# Sheet1.net
KiCad netlist of a schematic drawn in Altium Designer
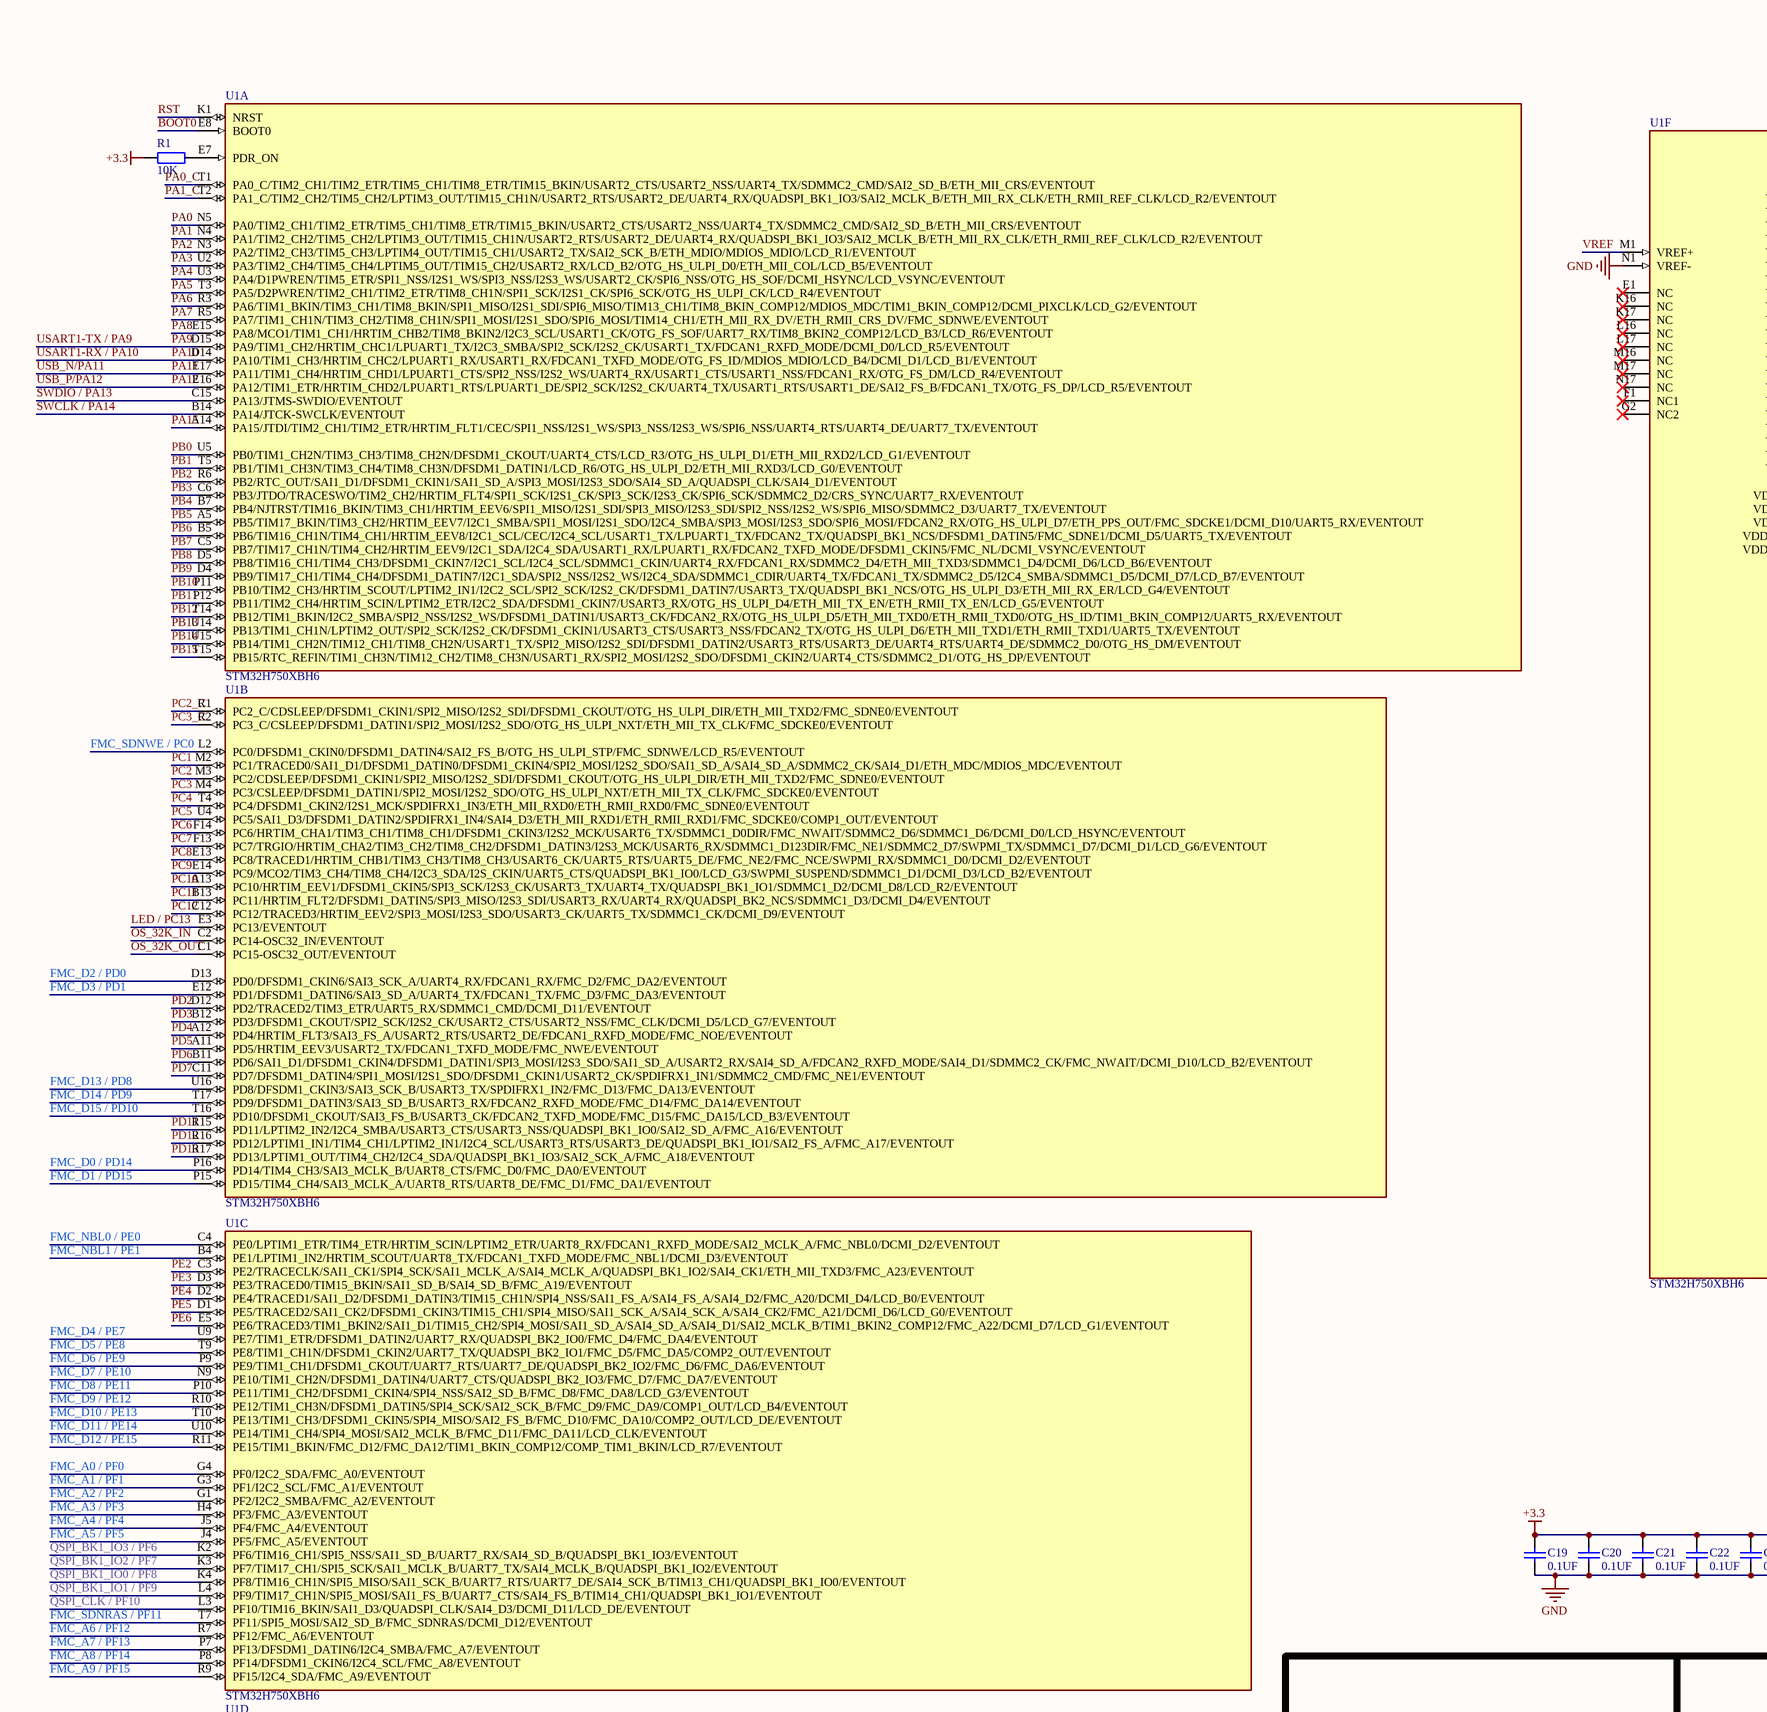
[diagram p0: Sheet1.SchDoc, top left]
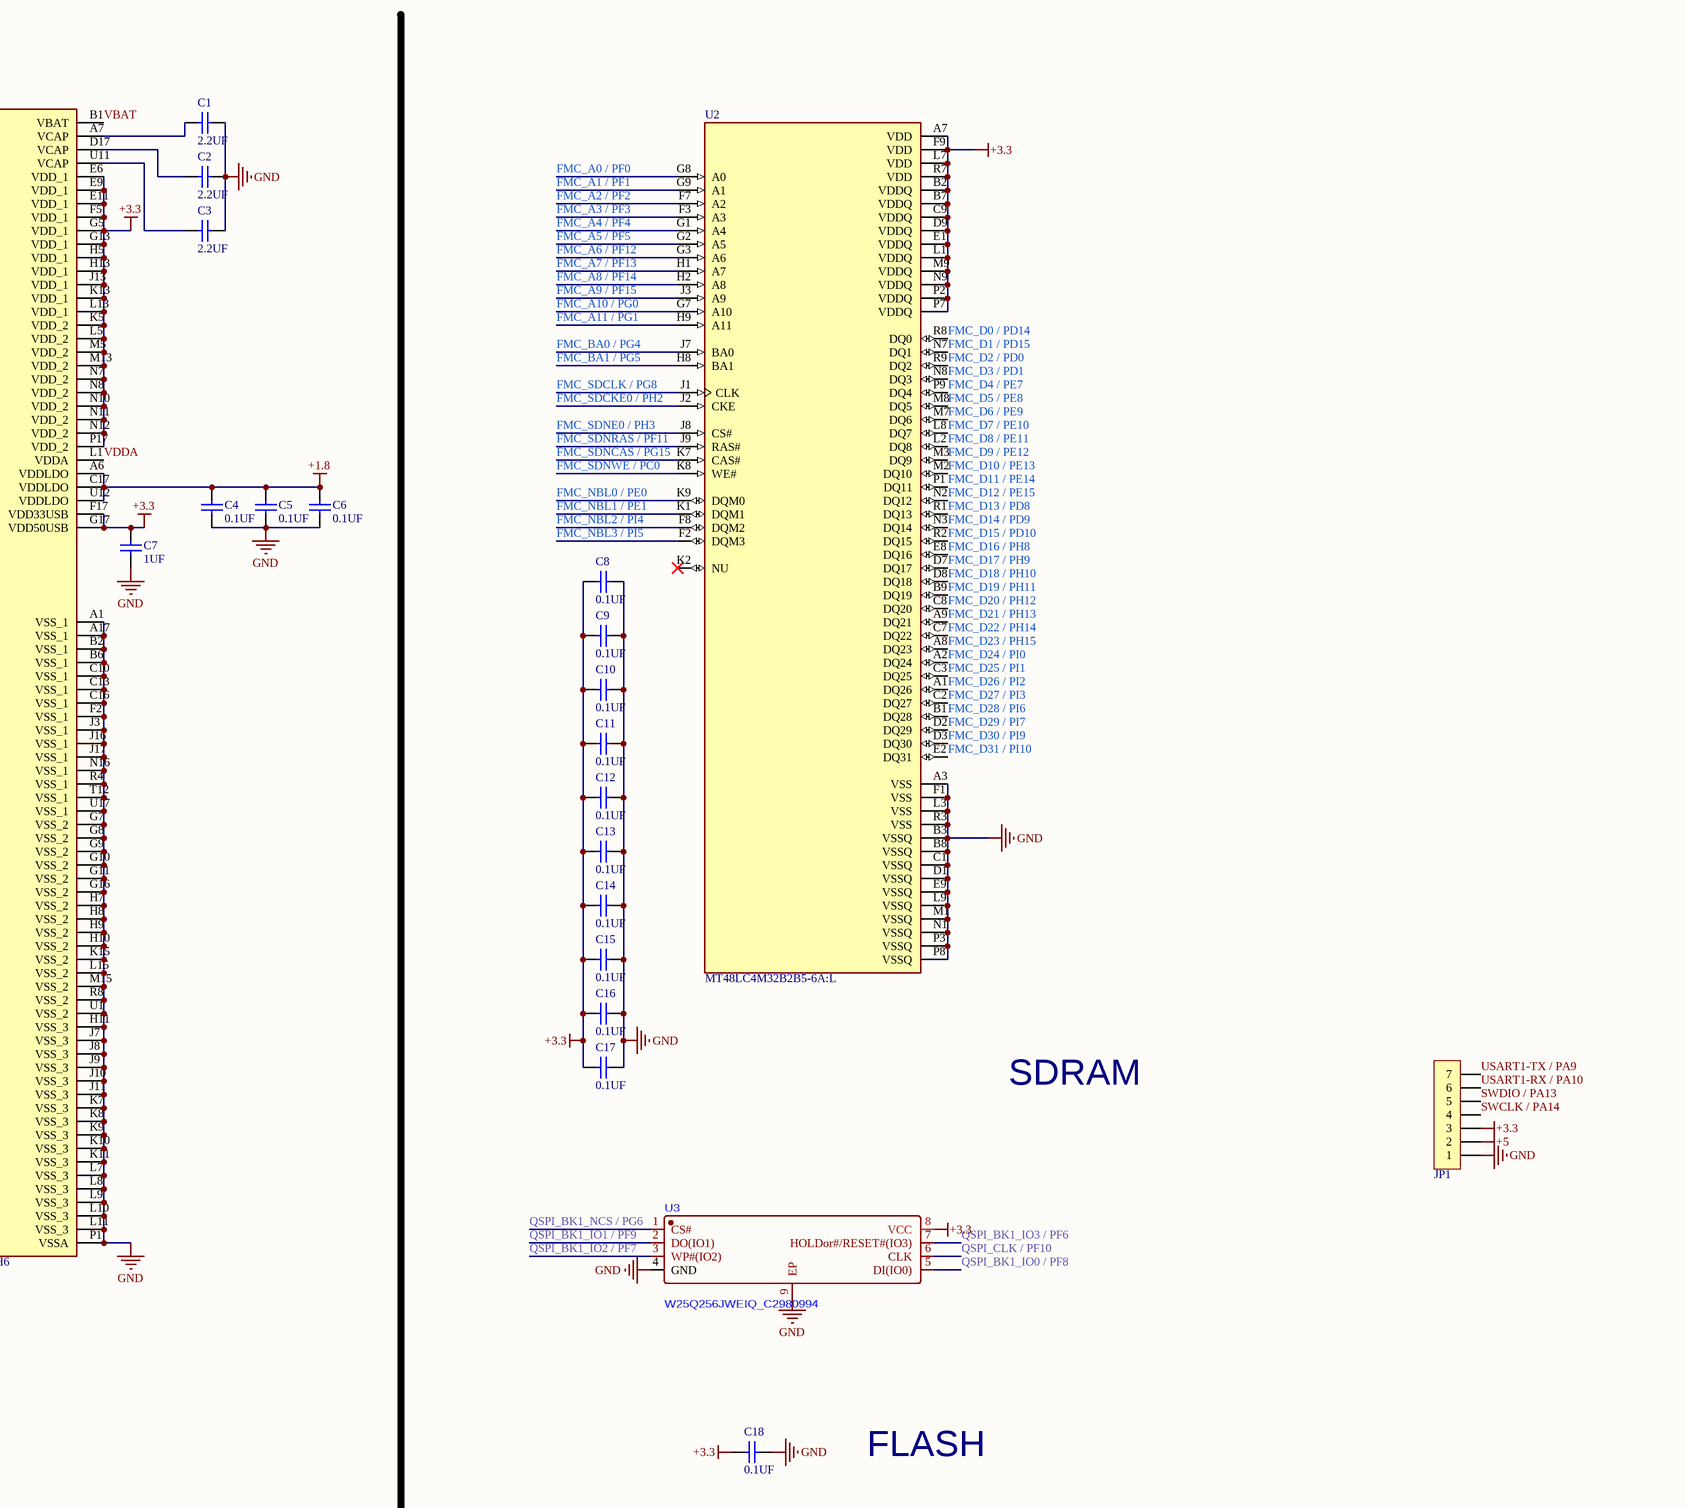
[diagram p1: Sheet1.SchDoc, top right]
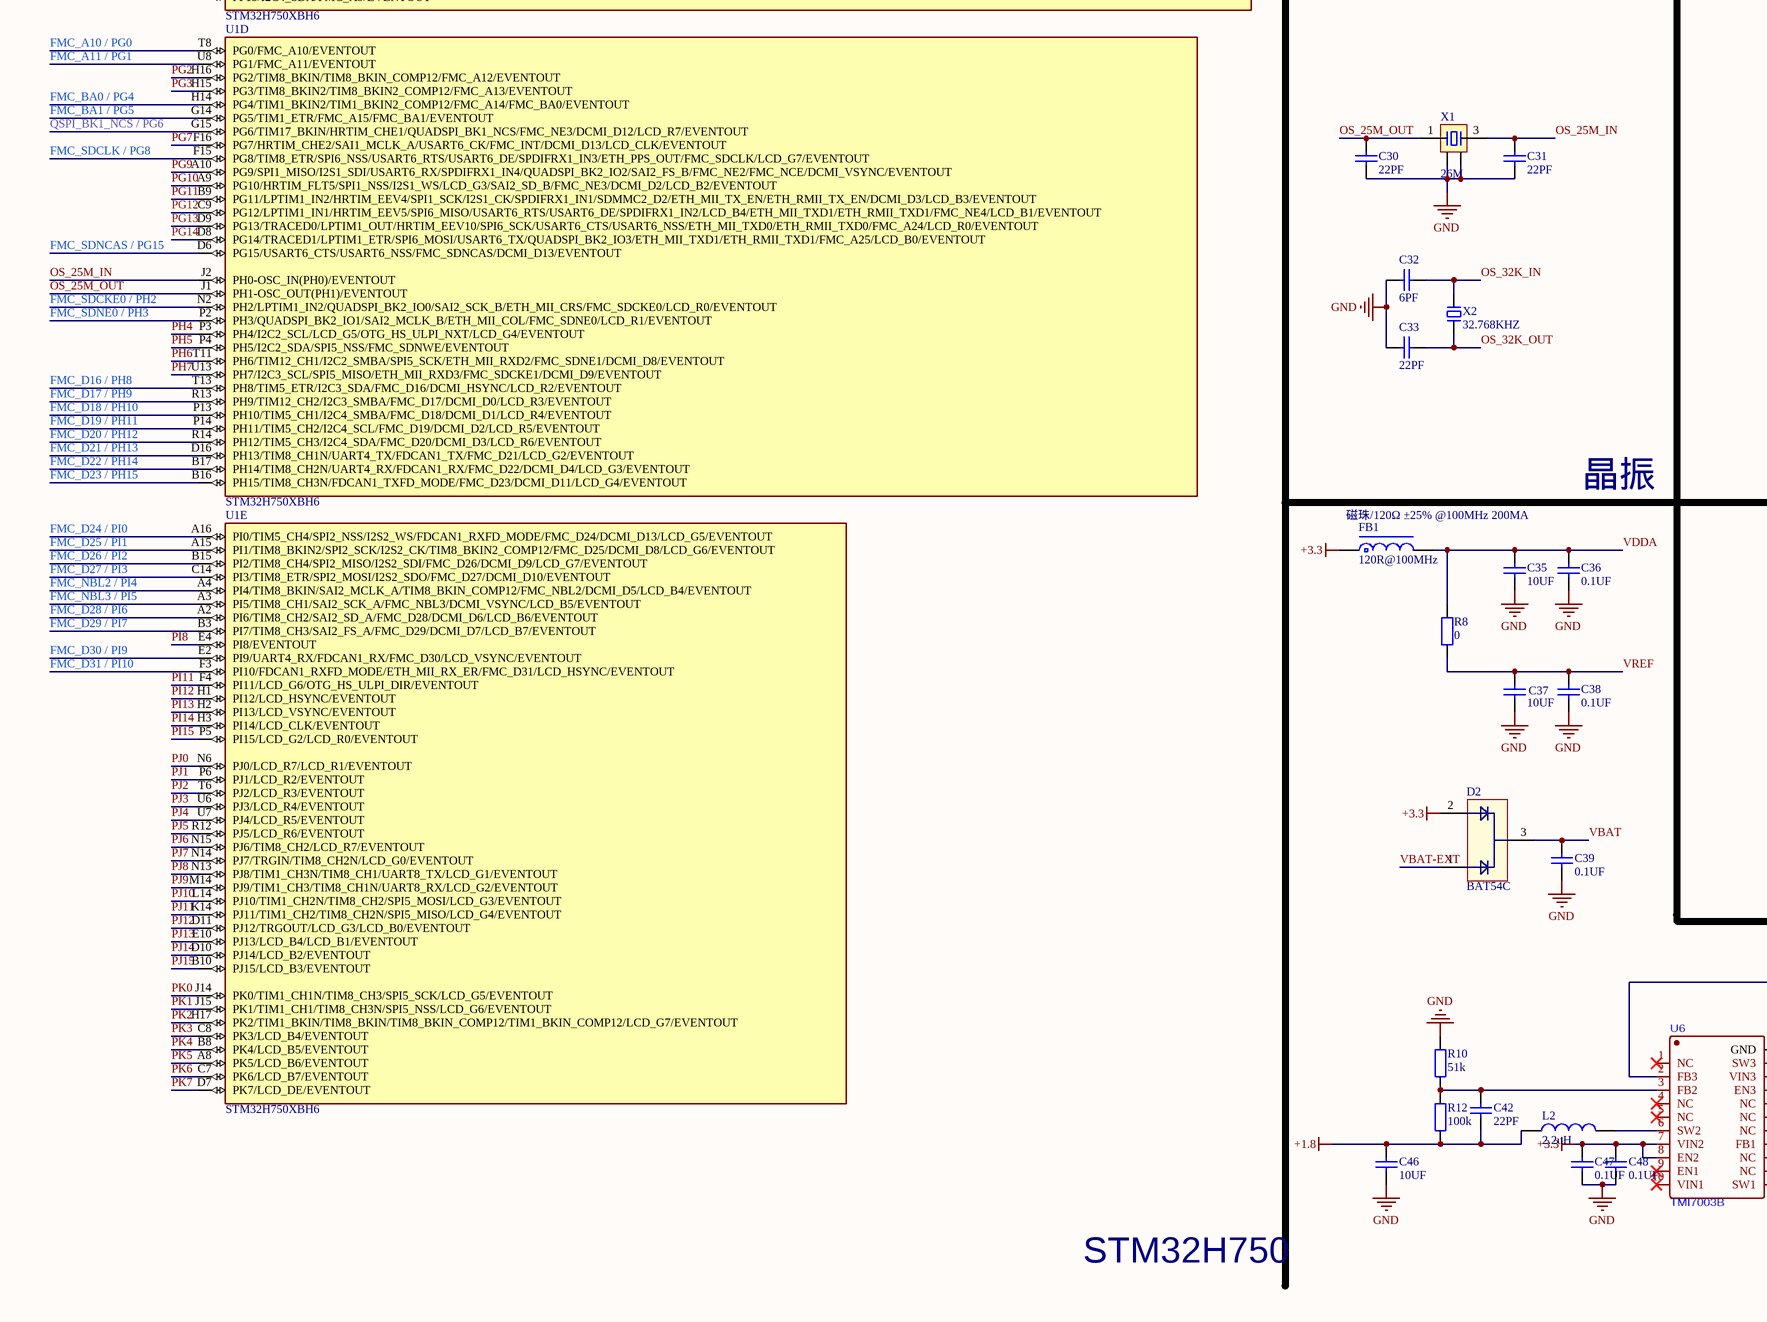
[diagram p2: Sheet1.SchDoc, bottom left]
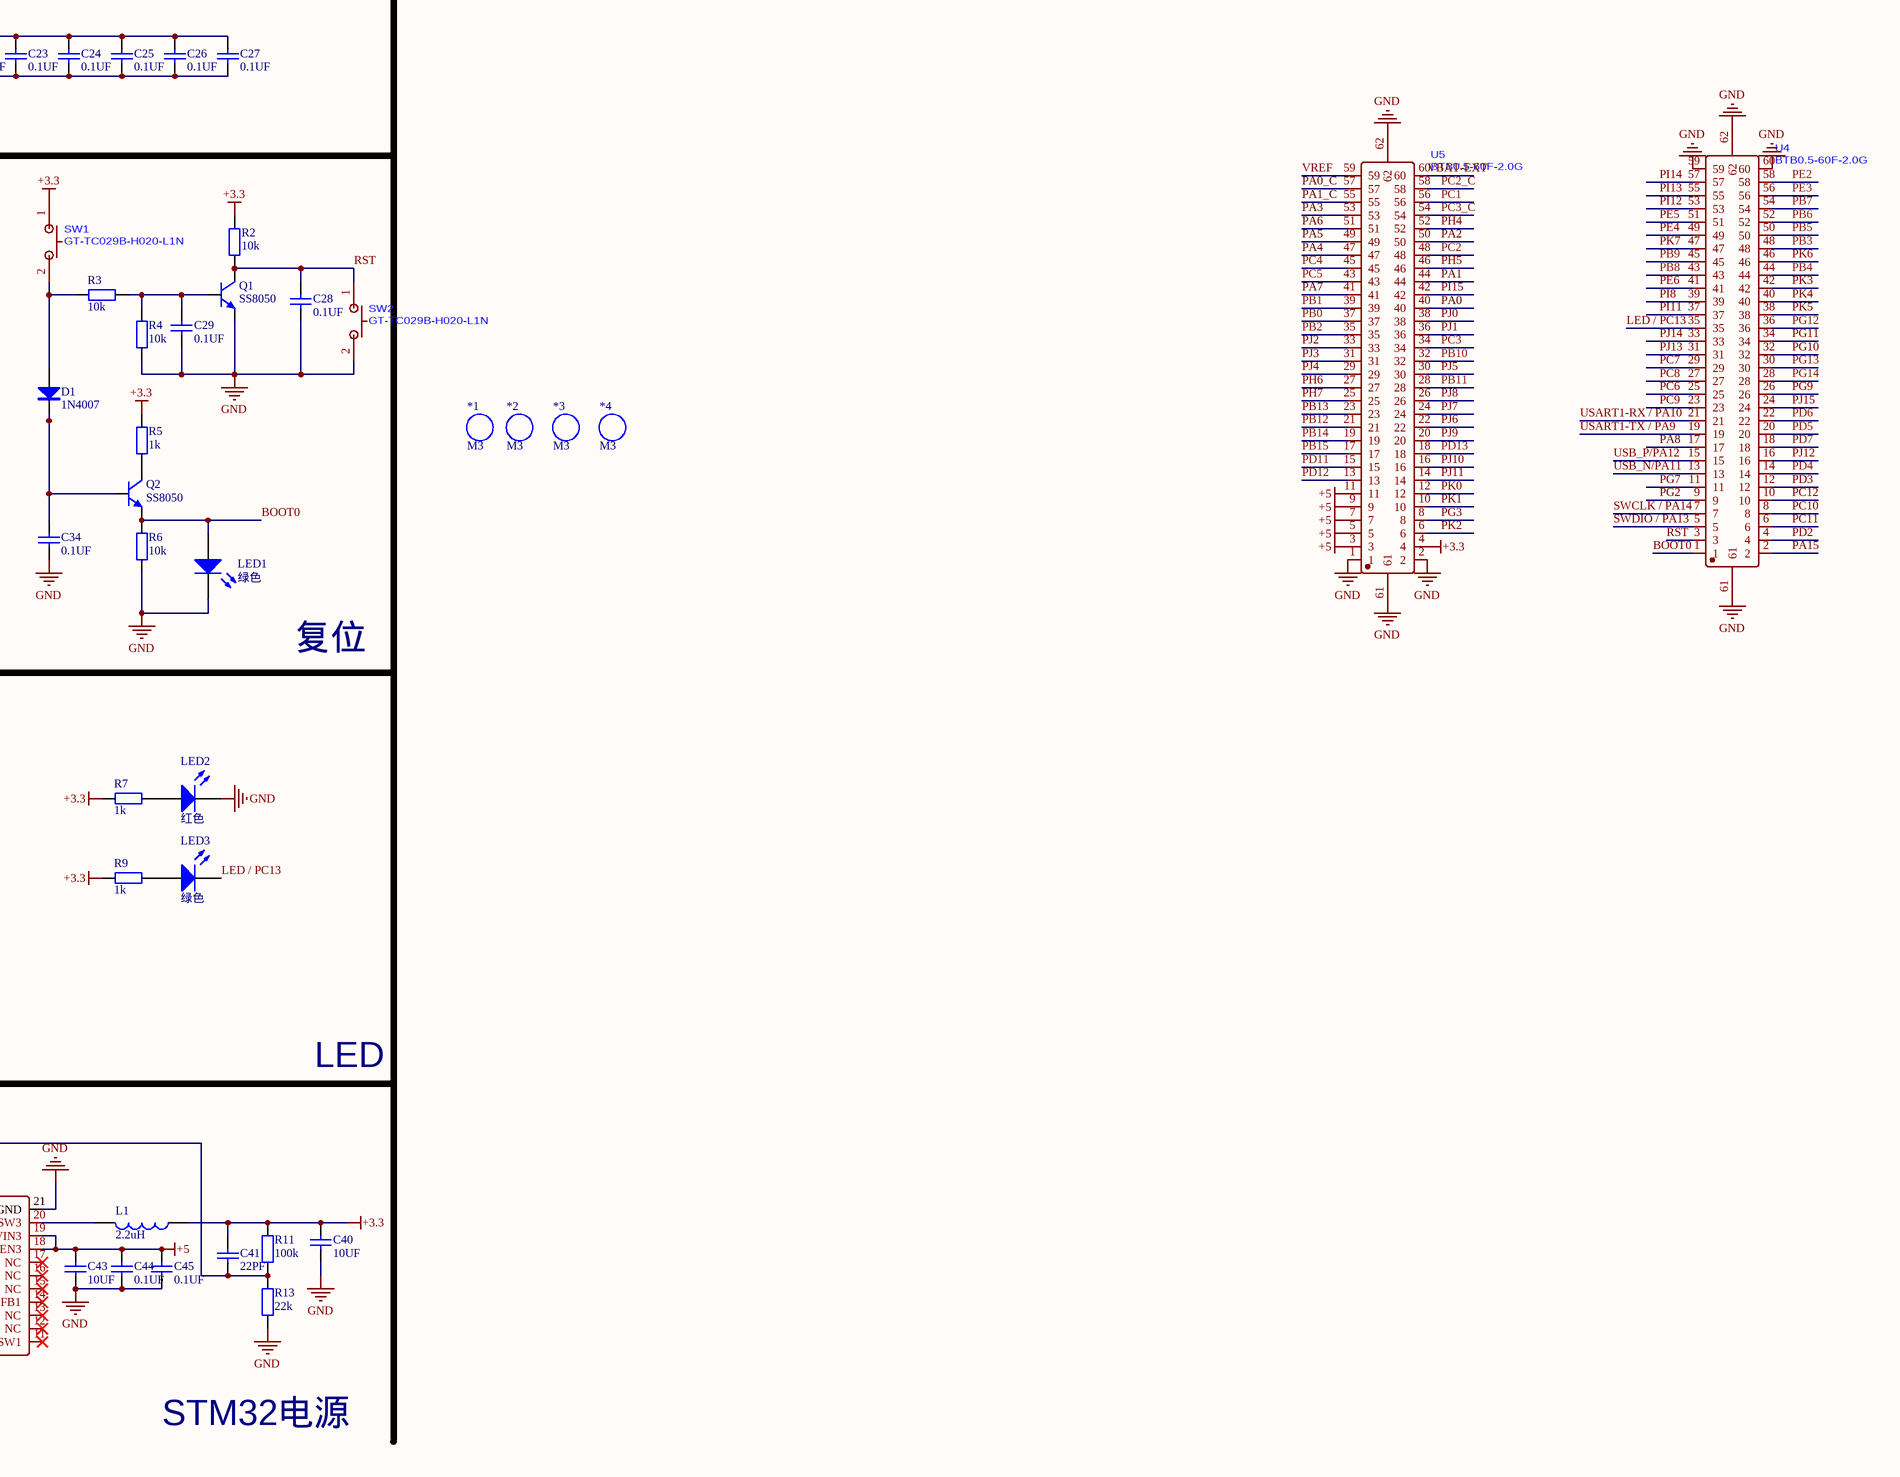
[diagram p3: Sheet1.SchDoc, bottom right]

(export (version "E")
  (design (tool "Eeschema 10.0.6"))
  (components
    (comp (ref "*1")
      (value "M3")
      (footprint "PCB1:M3 125X200")
      (description "铜柱孔")
      (libsource (lib "STM32H750核心板") (part "M3"))
    )
    (comp (ref "*2")
      (value "M3")
      (footprint "PCB1:M3 125X200")
      (description "铜柱孔")
      (libsource (lib "STM32H750核心板") (part "M3"))
    )
    (comp (ref "*3")
      (value "M3")
      (footprint "PCB1:M3 125X200")
      (description "铜柱孔")
      (libsource (lib "STM32H750核心板") (part "M3"))
    )
    (comp (ref "*4")
      (value "M3")
      (footprint "PCB1:M3 125X200")
      (description "铜柱孔")
      (libsource (lib "STM32H750核心板") (part "M3"))
    )
    (comp (ref "C1")
      (value "2.2UF")
      (footprint "PCB1:C0402_L")
      (description "贴片电容/MLCC电容")
      (libsource (lib "STM32H750核心板") (part "C"))
    )
    (comp (ref "C2")
      (value "2.2UF")
      (footprint "PCB1:C0402_L")
      (description "贴片电容/MLCC电容")
      (libsource (lib "STM32H750核心板") (part "C"))
    )
    (comp (ref "C3")
      (value "2.2UF")
      (footprint "PCB1:C0402_L")
      (description "贴片电容/MLCC电容")
      (libsource (lib "STM32H750核心板") (part "C"))
    )
    (comp (ref "C4")
      (value "0.1UF")
      (footprint "PCB1:C0402_L")
      (description "贴片电容/MLCC电容")
      (libsource (lib "STM32H750核心板") (part "C"))
    )
    (comp (ref "C5")
      (value "0.1UF")
      (footprint "PCB1:C0402_L")
      (description "贴片电容/MLCC电容")
      (libsource (lib "STM32H750核心板") (part "C"))
    )
    (comp (ref "C6")
      (value "0.1UF")
      (footprint "PCB1:C0402_L")
      (description "贴片电容/MLCC电容")
      (libsource (lib "STM32H750核心板") (part "C"))
    )
    (comp (ref "C7")
      (value "1UF")
      (footprint "PCB1:C0402_L")
      (description "贴片电容/MLCC电容")
      (libsource (lib "STM32H750核心板") (part "C"))
    )
    (comp (ref "C8")
      (value "0.1UF")
      (footprint "PCB1:C0402_M")
      (description "贴片电容/MLCC电容")
      (libsource (lib "STM32H750核心板") (part "C"))
    )
    (comp (ref "C9")
      (value "0.1UF")
      (footprint "PCB1:C0402_M")
      (description "贴片电容/MLCC电容")
      (libsource (lib "STM32H750核心板") (part "C"))
    )
    (comp (ref "C10")
      (value "0.1UF")
      (footprint "PCB1:C0402_M")
      (description "贴片电容/MLCC电容")
      (libsource (lib "STM32H750核心板") (part "C"))
    )
    (comp (ref "C11")
      (value "0.1UF")
      (footprint "PCB1:C0402_M")
      (description "贴片电容/MLCC电容")
      (libsource (lib "STM32H750核心板") (part "C"))
    )
    (comp (ref "C12")
      (value "0.1UF")
      (footprint "PCB1:C0402_M")
      (description "贴片电容/MLCC电容")
      (libsource (lib "STM32H750核心板") (part "C"))
    )
    (comp (ref "C13")
      (value "0.1UF")
      (footprint "PCB1:C0402_M")
      (description "贴片电容/MLCC电容")
      (libsource (lib "STM32H750核心板") (part "C"))
    )
    (comp (ref "C14")
      (value "0.1UF")
      (footprint "PCB1:C0402_M")
      (description "贴片电容/MLCC电容")
      (libsource (lib "STM32H750核心板") (part "C"))
    )
    (comp (ref "C15")
      (value "0.1UF")
      (footprint "PCB1:C0402_M")
      (description "贴片电容/MLCC电容")
      (libsource (lib "STM32H750核心板") (part "C"))
    )
    (comp (ref "C16")
      (value "0.1UF")
      (footprint "PCB1:C0402_M")
      (description "贴片电容/MLCC电容")
      (libsource (lib "STM32H750核心板") (part "C"))
    )
    (comp (ref "C17")
      (value "0.1UF")
      (footprint "PCB1:C0402_M")
      (description "贴片电容/MLCC电容")
      (libsource (lib "STM32H750核心板") (part "C"))
    )
    (comp (ref "C18")
      (value "0.1UF")
      (footprint "PCB1:C0402_L")
      (description "贴片电容/MLCC电容")
      (libsource (lib "STM32H750核心板") (part "C"))
    )
    (comp (ref "C19")
      (value "0.1UF")
      (footprint "PCB1:C0402_M")
      (description "贴片电容/MLCC电容")
      (libsource (lib "STM32H750核心板") (part "C"))
    )
    (comp (ref "C20")
      (value "0.1UF")
      (footprint "PCB1:C0402_M")
      (description "贴片电容/MLCC电容")
      (libsource (lib "STM32H750核心板") (part "C"))
    )
    (comp (ref "C21")
      (value "0.1UF")
      (footprint "PCB1:C0402_M")
      (description "贴片电容/MLCC电容")
      (libsource (lib "STM32H750核心板") (part "C"))
    )
    (comp (ref "C22")
      (value "0.1UF")
      (footprint "PCB1:C0402_M")
      (description "贴片电容/MLCC电容")
      (libsource (lib "STM32H750核心板") (part "C"))
    )
    (comp (ref "C23")
      (value "0.1UF")
      (footprint "PCB1:C0402_M")
      (description "贴片电容/MLCC电容")
      (libsource (lib "STM32H750核心板") (part "C"))
    )
    (comp (ref "C24")
      (value "0.1UF")
      (footprint "PCB1:C0402_M")
      (description "贴片电容/MLCC电容")
      (libsource (lib "STM32H750核心板") (part "C"))
    )
    (comp (ref "C25")
      (value "0.1UF")
      (footprint "PCB1:C0402_M")
      (description "贴片电容/MLCC电容")
      (libsource (lib "STM32H750核心板") (part "C"))
    )
    (comp (ref "C26")
      (value "0.1UF")
      (footprint "PCB1:C0402_M")
      (description "贴片电容/MLCC电容")
      (libsource (lib "STM32H750核心板") (part "C"))
    )
    (comp (ref "C27")
      (value "0.1UF")
      (footprint "PCB1:C0402_M")
      (description "贴片电容/MLCC电容")
      (libsource (lib "STM32H750核心板") (part "C"))
    )
    (comp (ref "C28")
      (value "0.1UF")
      (footprint "PCB1:C0402_L")
      (description "贴片电容/MLCC电容")
      (libsource (lib "STM32H750核心板") (part "C"))
    )
    (comp (ref "C29")
      (value "0.1UF")
      (footprint "PCB1:C0402_L")
      (description "贴片电容/MLCC电容")
      (libsource (lib "STM32H750核心板") (part "C"))
    )
    (comp (ref "C30")
      (value "22PF")
      (footprint "PCB1:C0402_L")
      (description "贴片电容/MLCC电容")
      (libsource (lib "STM32H750核心板") (part "C"))
    )
    (comp (ref "C31")
      (value "22PF")
      (footprint "PCB1:C0402_L")
      (description "贴片电容/MLCC电容")
      (libsource (lib "STM32H750核心板") (part "C"))
    )
    (comp (ref "C32")
      (value "6PF")
      (footprint "PCB1:C0402_L")
      (description "贴片电容/MLCC电容")
      (libsource (lib "STM32H750核心板") (part "C"))
    )
    (comp (ref "C33")
      (value "22PF")
      (footprint "PCB1:C0402_L")
      (description "贴片电容/MLCC电容")
      (libsource (lib "STM32H750核心板") (part "C"))
    )
    (comp (ref "C34")
      (value "0.1UF")
      (footprint "PCB1:C0402_L")
      (description "贴片电容/MLCC电容")
      (libsource (lib "STM32H750核心板") (part "C"))
    )
    (comp (ref "C35")
      (value "10UF")
      (footprint "PCB1:C0603_L")
      (description "贴片电容/MLCC电容")
      (libsource (lib "STM32H750核心板") (part "C"))
    )
    (comp (ref "C36")
      (value "0.1UF")
      (footprint "PCB1:C0402_L")
      (description "贴片电容/MLCC电容")
      (libsource (lib "STM32H750核心板") (part "C"))
    )
    (comp (ref "C37")
      (value "10UF")
      (footprint "PCB1:C0603_L")
      (description "贴片电容/MLCC电容")
      (libsource (lib "STM32H750核心板") (part "C"))
    )
    (comp (ref "C38")
      (value "0.1UF")
      (footprint "PCB1:C0402_L")
      (description "贴片电容/MLCC电容")
      (libsource (lib "STM32H750核心板") (part "C"))
    )
    (comp (ref "C39")
      (value "0.1UF")
      (footprint "PCB1:C0402_L")
      (description "贴片电容/MLCC电容")
      (libsource (lib "STM32H750核心板") (part "C"))
    )
    (comp (ref "C40")
      (value "10UF")
      (footprint "PCB1:C0603_L")
      (description "贴片电容/MLCC电容")
      (libsource (lib "STM32H750核心板") (part "C"))
    )
    (comp (ref "C41")
      (value "22PF")
      (footprint "PCB1:C0402_L")
      (description "贴片电容/MLCC电容")
      (libsource (lib "STM32H750核心板") (part "C"))
    )
    (comp (ref "C42")
      (value "22PF")
      (footprint "PCB1:C0402_L")
      (description "贴片电容/MLCC电容")
      (libsource (lib "STM32H750核心板") (part "C"))
    )
    (comp (ref "C43")
      (value "10UF")
      (footprint "PCB1:C0603_L")
      (description "贴片电容/MLCC电容")
      (libsource (lib "STM32H750核心板") (part "C"))
    )
    (comp (ref "C44")
      (value "0.1UF")
      (footprint "PCB1:C0402_L")
      (description "贴片电容/MLCC电容")
      (libsource (lib "STM32H750核心板") (part "C"))
    )
    (comp (ref "C45")
      (value "0.1UF")
      (footprint "PCB1:C0402_L")
      (description "贴片电容/MLCC电容")
      (libsource (lib "STM32H750核心板") (part "C"))
    )
    (comp (ref "C46")
      (value "10UF")
      (footprint "PCB1:C0603_L")
      (description "贴片电容/MLCC电容")
      (libsource (lib "STM32H750核心板") (part "C"))
    )
    (comp (ref "C47")
      (value "0.1UF")
      (footprint "PCB1:C0402_L")
      (description "贴片电容/MLCC电容")
      (libsource (lib "STM32H750核心板") (part "C"))
    )
    (comp (ref "C48")
      (value "0.1UF")
      (footprint "PCB1:C0402_L")
      (description "贴片电容/MLCC电容")
      (libsource (lib "STM32H750核心板") (part "C"))
    )
    (comp (ref "D1")
      (value "1N4007")
      (footprint "PCB1:SOD-123")
      (description "整流二极管")
      (libsource (lib "STM32H750核心板") (part "1N4007"))
    )
    (comp (ref "D2")
      (value "BAT54C")
      (footprint "PCB1:SOT23-3N")
      (description "两路肖特基二极管")
      (libsource (lib "STM32H750核心板") (part "BAT54C"))
    )
    (comp (ref "FB1")
      (value "120R@100MHz")
      (footprint "PCB1:FB0603")
      (description "贴片磁珠")
      (libsource (lib "STM32H750核心板") (part "FB"))
    )
    (comp (ref "JP1")
      (value "CON-6P")
      (footprint "PCB1:SH1.0-LT-7P")
      (description "7P连接器")
      (libsource (lib "STM32H750核心板") (part "Header 7"))
    )
    (comp (ref "L1")
      (value "2.2uH")
      (footprint "PCB1:L0805")
      (description "贴片小功率电感")
      (libsource (lib "STM32H750核心板") (part "L"))
    )
    (comp (ref "L2")
      (value "2.2uH")
      (footprint "PCB1:L0805")
      (description "贴片小功率电感")
      (libsource (lib "STM32H750核心板") (part "L"))
    )
    (comp (ref "LED1")
      (value "绿色")
      (footprint "PCB1:LED0603_G")
      (description "贴片LED")
      (libsource (lib "STM32H750核心板") (part "LED"))
    )
    (comp (ref "LED2")
      (value "红色")
      (footprint "PCB1:LED0603_G")
      (description "贴片LED")
      (libsource (lib "STM32H750核心板") (part "LED"))
    )
    (comp (ref "LED3")
      (value "绿色")
      (footprint "PCB1:LED0603_G")
      (description "贴片LED")
      (libsource (lib "STM32H750核心板") (part "LED"))
    )
    (comp (ref "Q1")
      (value "SS8050")
      (footprint "PCB1:SOT23-3N")
      (description "高频放大-NPN型")
      (libsource (lib "STM32H750核心板") (part "8050-SMD"))
    )
    (comp (ref "Q2")
      (value "SS8050")
      (footprint "PCB1:SOT23-3N")
      (description "高频放大-NPN型")
      (libsource (lib "STM32H750核心板") (part "8050-SMD"))
    )
    (comp (ref "R1")
      (value "10K")
      (footprint "PCB1:R0402_L")
      (description "贴片电阻")
      (libsource (lib "STM32H750核心板") (part "R"))
    )
    (comp (ref "R2")
      (value "10k")
      (footprint "PCB1:R0402_L")
      (description "贴片电阻")
      (libsource (lib "STM32H750核心板") (part "R"))
    )
    (comp (ref "R3")
      (value "10k")
      (footprint "PCB1:R0402_L")
      (description "贴片电阻")
      (libsource (lib "STM32H750核心板") (part "R"))
    )
    (comp (ref "R4")
      (value "10k")
      (footprint "PCB1:R0402_L")
      (description "贴片电阻")
      (libsource (lib "STM32H750核心板") (part "R"))
    )
    (comp (ref "R5")
      (value "1k")
      (footprint "PCB1:R0402_L")
      (description "贴片电阻")
      (libsource (lib "STM32H750核心板") (part "R"))
    )
    (comp (ref "R6")
      (value "10k")
      (footprint "PCB1:R0402_L")
      (description "贴片电阻")
      (libsource (lib "STM32H750核心板") (part "R"))
    )
    (comp (ref "R7")
      (value "1k")
      (footprint "PCB1:R0402_L")
      (description "贴片电阻")
      (libsource (lib "STM32H750核心板") (part "R"))
    )
    (comp (ref "R8")
      (value "0")
      (footprint "PCB1:R0402_L")
      (description "贴片电阻")
      (libsource (lib "STM32H750核心板") (part "R"))
    )
    (comp (ref "R9")
      (value "1k")
      (footprint "PCB1:R0402_L")
      (description "贴片电阻")
      (libsource (lib "STM32H750核心板") (part "R"))
    )
    (comp (ref "R10")
      (value "51k")
      (footprint "PCB1:R0402_L")
      (description "贴片电阻")
      (libsource (lib "STM32H750核心板") (part "R"))
    )
    (comp (ref "R11")
      (value "100k")
      (footprint "PCB1:R0402_L")
      (description "贴片电阻")
      (libsource (lib "STM32H750核心板") (part "R"))
    )
    (comp (ref "R12")
      (value "100k")
      (footprint "PCB1:R0402_L")
      (description "贴片电阻")
      (libsource (lib "STM32H750核心板") (part "R"))
    )
    (comp (ref "R13")
      (value "22k")
      (footprint "PCB1:R0402_L")
      (description "贴片电阻")
      (libsource (lib "STM32H750核心板") (part "R"))
    )
    (comp (ref "SW1")
      (value "GT-TC029B-H020-L1N")
      (footprint "PCB1:SW-SMD_L3.9-W2.9-P4.15-LS5.0")
      (libsource (lib "STM32H750核心板") (part "GT-TC029B-H020-L1N"))
    )
    (comp (ref "SW2")
      (value "GT-TC029B-H020-L1N")
      (footprint "PCB1:SW-SMD_L3.9-W2.9-P4.15-LS5.0")
      (libsource (lib "STM32H750核心板") (part "GT-TC029B-H020-L1N"))
    )
    (comp (ref "U1")
      (value "STM32H750XBH6")
      (footprint "PCB1:IC_STM32H750XBH6")
      (libsource (lib "STM32H750核心板") (part "STM32H750XBH6"))
    )
    (comp (ref "U2")
      (value "MT48LC4M32B2B5-6A:L")
      (footprint "PCB1:BGA90C80P9X15_800X1300X100N")
      (description "SDRAM Memory IC 128Mb _4M x 32_ Parallel 167MHz 5.4ns 90-VFBGA _8x13_")
      (libsource (lib "STM32H750核心板") (part "MT48LC4M32B2B5-6A{colon}L"))
    )
    (comp (ref "U3")
      (value "W25Q256JWEIQ_C2980994")
      (footprint "PCB1:WSON-8_L8.0-W6.0-P1.27-TL-EP-1")
      (libsource (lib "STM32H750核心板") (part "W25Q256JWEIQ_C2980994"))
    )
    (comp (ref "U4")
      (value "BTB0.5-60F-2.0G")
      (footprint "PCB1:CONN-SMD_60P-P0.50_BTB0.5-60F-2.0G")
      (libsource (lib "STM32H750核心板") (part "BTB0.5-60F-2.0G"))
    )
    (comp (ref "U5")
      (value "BTB0.5-60F-2.0G")
      (footprint "PCB1:CONN-SMD_60P-P0.50_BTB0.5-60F-2.0G")
      (libsource (lib "STM32H750核心板") (part "BTB0.5-60F-2.0G"))
    )
    (comp (ref "U6")
      (value "TMI7003B")
      (footprint "PCB1:QFN-20_L3.0-W3.0-P0.40-BL-EP1.7")
      (libsource (lib "STM32H750核心板") (part "TMI7003B"))
    )
    (comp (ref "X1")
      (value "26M")
      (footprint "PCB1:XTAL-3225-4P")
      (description "4脚无源晶振(谐振器）")
      (libsource (lib "STM32H750核心板") (part "XTAL-4P"))
    )
    (comp (ref "X2")
      (value "32.768KHZ")
      (footprint "PCB1:XTAL-3215-2P")
      (description "2脚无源晶振(谐振器）")
      (libsource (lib "STM32H750核心板") (part "XTAL-2P"))
    )
  )
  (nets
    (net (code "1") (name "+1.8") (class "Default")
      (node (ref "C4") (pin "1") (pinfunction "1_1") (pintype "passive"))
      (node (ref "C42") (pin "2") (pinfunction "2_2") (pintype "passive"))
      (node (ref "C46") (pin "1") (pinfunction "1_1") (pintype "passive"))
      (node (ref "C5") (pin "1") (pinfunction "1_1") (pintype "passive"))
      (node (ref "C6") (pin "1") (pinfunction "1_1") (pintype "passive"))
      (node (ref "L2") (pin "1") (pinfunction "1_1") (pintype "passive"))
      (node (ref "R12") (pin "1") (pinfunction "1_1") (pintype "passive"))
      (node (ref "U1") (pin "A6") (pinfunction "VDDLDO_A6") (pintype "power_in"))
      (node (ref "U1") (pin "C17") (pinfunction "VDDLDO_C17") (pintype "power_in"))
      (node (ref "U1") (pin "U12") (pinfunction "VDDLDO_U12") (pintype "power_in"))
    )
    (net (code "2") (name "+3.3") (class "Default")
      (node (ref "C10") (pin "2") (pinfunction "2_2") (pintype "passive"))
      (node (ref "C11") (pin "2") (pinfunction "2_2") (pintype "passive"))
      (node (ref "C12") (pin "2") (pinfunction "2_2") (pintype "passive"))
      (node (ref "C13") (pin "2") (pinfunction "2_2") (pintype "passive"))
      (node (ref "C14") (pin "2") (pinfunction "2_2") (pintype "passive"))
      (node (ref "C15") (pin "2") (pinfunction "2_2") (pintype "passive"))
      (node (ref "C16") (pin "2") (pinfunction "2_2") (pintype "passive"))
      (node (ref "C17") (pin "2") (pinfunction "2_2") (pintype "passive"))
      (node (ref "C18") (pin "2") (pinfunction "2_2") (pintype "passive"))
      (node (ref "C19") (pin "2") (pinfunction "2_2") (pintype "passive"))
      (node (ref "C20") (pin "2") (pinfunction "2_2") (pintype "passive"))
      (node (ref "C21") (pin "2") (pinfunction "2_2") (pintype "passive"))
      (node (ref "C22") (pin "2") (pinfunction "2_2") (pintype "passive"))
      (node (ref "C23") (pin "2") (pinfunction "2_2") (pintype "passive"))
      (node (ref "C24") (pin "2") (pinfunction "2_2") (pintype "passive"))
      (node (ref "C25") (pin "2") (pinfunction "2_2") (pintype "passive"))
      (node (ref "C26") (pin "2") (pinfunction "2_2") (pintype "passive"))
      (node (ref "C27") (pin "2") (pinfunction "2_2") (pintype "passive"))
      (node (ref "C40") (pin "2") (pinfunction "2_2") (pintype "passive"))
      (node (ref "C41") (pin "2") (pinfunction "2_2") (pintype "passive"))
      (node (ref "C47") (pin "2") (pinfunction "2_2") (pintype "passive"))
      (node (ref "C48") (pin "2") (pinfunction "2_2") (pintype "passive"))
      (node (ref "C7") (pin "2") (pinfunction "2_2") (pintype "passive"))
      (node (ref "C8") (pin "2") (pinfunction "2_2") (pintype "passive"))
      (node (ref "C9") (pin "2") (pinfunction "2_2") (pintype "passive"))
      (node (ref "D2") (pin "2") (pinfunction "2_2") (pintype "passive"))
      (node (ref "FB1") (pin "1") (pinfunction "1_1") (pintype "passive"))
      (node (ref "JP1") (pin "3") (pinfunction "3_3") (pintype "passive"))
      (node (ref "L1") (pin "1") (pinfunction "1_1") (pintype "passive"))
      (node (ref "R1") (pin "1") (pinfunction "1_1") (pintype "passive"))
      (node (ref "R11") (pin "1") (pinfunction "1_1") (pintype "passive"))
      (node (ref "R2") (pin "2") (pinfunction "2_2") (pintype "passive"))
      (node (ref "R5") (pin "2") (pinfunction "2_2") (pintype "passive"))
      (node (ref "R7") (pin "1") (pinfunction "1_1") (pintype "passive"))
      (node (ref "R9") (pin "1") (pinfunction "1_1") (pintype "passive"))
      (node (ref "SW1") (pin "1") (pinfunction "1_1") (pintype "passive"))
      (node (ref "U1") (pin "E11") (pinfunction "VDD_1_E11") (pintype "power_in"))
      (node (ref "U1") (pin "E6") (pinfunction "VDD_1_E6") (pintype "power_in"))
      (node (ref "U1") (pin "E9") (pinfunction "VDD_1_E9") (pintype "power_in"))
      (node (ref "U1") (pin "F17") (pinfunction "VDD33USB_F17") (pintype "power_in"))
      (node (ref "U1") (pin "F5") (pinfunction "VDD_1_F5") (pintype "power_in"))
      (node (ref "U1") (pin "G13") (pinfunction "VDD_1_G13") (pintype "power_in"))
      (node (ref "U1") (pin "G17") (pinfunction "VDD50USB_G17") (pintype "power_in"))
      (node (ref "U1") (pin "G5") (pinfunction "VDD_1_G5") (pintype "power_in"))
      (node (ref "U1") (pin "H13") (pinfunction "VDD_1_H13") (pintype "power_in"))
      (node (ref "U1") (pin "H5") (pinfunction "VDD_1_H5") (pintype "power_in"))
      (node (ref "U1") (pin "J13") (pinfunction "VDD_1_J13") (pintype "power_in"))
      (node (ref "U1") (pin "K13") (pinfunction "VDD_1_K13") (pintype "power_in"))
      (node (ref "U1") (pin "K5") (pinfunction "VDD_2_K5") (pintype "power_in"))
      (node (ref "U1") (pin "L13") (pinfunction "VDD_1_L13") (pintype "power_in"))
      (node (ref "U1") (pin "L5") (pinfunction "VDD_2_L5") (pintype "power_in"))
      (node (ref "U1") (pin "M13") (pinfunction "VDD_2_M13") (pintype "power_in"))
      (node (ref "U1") (pin "M5") (pinfunction "VDD_2_M5") (pintype "power_in"))
      (node (ref "U1") (pin "N10") (pinfunction "VDD_2_N10") (pintype "power_in"))
      (node (ref "U1") (pin "N11") (pinfunction "VDD_2_N11") (pintype "power_in"))
      (node (ref "U1") (pin "N12") (pinfunction "VDD_2_N12") (pintype "power_in"))
      (node (ref "U1") (pin "N7") (pinfunction "VDD_2_N7") (pintype "power_in"))
      (node (ref "U1") (pin "N8") (pinfunction "VDD_2_N8") (pintype "power_in"))
      (node (ref "U1") (pin "P17") (pinfunction "VDD_2_P17") (pintype "power_in"))
      (node (ref "U2") (pin "A7") (pinfunction "VDD_A7") (pintype "power_in"))
      (node (ref "U2") (pin "B2") (pinfunction "VDDQ_B2") (pintype "power_in"))
      (node (ref "U2") (pin "B7") (pinfunction "VDDQ_B7") (pintype "power_in"))
      (node (ref "U2") (pin "C9") (pinfunction "VDDQ_C9") (pintype "power_in"))
      (node (ref "U2") (pin "D9") (pinfunction "VDDQ_D9") (pintype "power_in"))
      (node (ref "U2") (pin "E1") (pinfunction "VDDQ_E1") (pintype "power_in"))
      (node (ref "U2") (pin "F9") (pinfunction "VDD_F9") (pintype "power_in"))
      (node (ref "U2") (pin "L1") (pinfunction "VDDQ_L1") (pintype "power_in"))
      (node (ref "U2") (pin "L7") (pinfunction "VDD_L7") (pintype "power_in"))
      (node (ref "U2") (pin "M9") (pinfunction "VDDQ_M9") (pintype "power_in"))
      (node (ref "U2") (pin "N9") (pinfunction "VDDQ_N9") (pintype "power_in"))
      (node (ref "U2") (pin "P2") (pinfunction "VDDQ_P2") (pintype "power_in"))
      (node (ref "U2") (pin "P7") (pinfunction "VDDQ_P7") (pintype "power_in"))
      (node (ref "U2") (pin "R7") (pinfunction "VDD_R7") (pintype "power_in"))
      (node (ref "U3") (pin "8") (pinfunction "VCC_8") (pintype "passive"))
      (node (ref "U5") (pin "4") (pinfunction "4_4") (pintype "passive"))
      (node (ref "U6") (pin "7") (pinfunction "VIN2_7") (pintype "passive"))
      (node (ref "U6") (pin "8") (pinfunction "EN2_8") (pintype "passive"))
    )
    (net (code "3") (name "+5") (class "Default")
      (node (ref "C43") (pin "2") (pinfunction "2_2") (pintype "passive"))
      (node (ref "C44") (pin "2") (pinfunction "2_2") (pintype "passive"))
      (node (ref "C45") (pin "2") (pinfunction "2_2") (pintype "passive"))
      (node (ref "JP1") (pin "2") (pinfunction "2_2") (pintype "passive"))
      (node (ref "U5") (pin "11") (pinfunction "11_11") (pintype "passive"))
      (node (ref "U5") (pin "3") (pinfunction "3_3") (pintype "passive"))
      (node (ref "U5") (pin "5") (pinfunction "5_5") (pintype "passive"))
      (node (ref "U5") (pin "7") (pinfunction "7_7") (pintype "passive"))
      (node (ref "U5") (pin "9") (pinfunction "9_9") (pintype "passive"))
      (node (ref "U6") (pin "18") (pinfunction "EN3_18") (pintype "passive"))
      (node (ref "U6") (pin "19") (pinfunction "VIN3_19") (pintype "passive"))
    )
    (net (code "4") (name "/BOOT0") (class "Default")
      (node (ref "LED1") (pin "1") (pinfunction "A_1") (pintype "passive"))
      (node (ref "Q2") (pin "2") (pinfunction "E_2") (pintype "passive"))
      (node (ref "R6") (pin "2") (pinfunction "2_2") (pintype "passive"))
      (node (ref "U1") (pin "E8") (pinfunction "BOOT0_E8") (pintype "input"))
      (node (ref "U4") (pin "1") (pinfunction "1_1") (pintype "passive"))
    )
    (net (code "5") (name "/FMC_A0 {slash} PF0") (class "Default")
      (node (ref "U1") (pin "G4") (pinfunction "PF0/I2C2_SDA/FMC_A0/EVENTOUT_G4") (pintype "bidirectional"))
      (node (ref "U2") (pin "G8") (pinfunction "A0_G8") (pintype "input"))
    )
    (net (code "6") (name "/FMC_A1 {slash} PF1") (class "Default")
      (node (ref "U1") (pin "G3") (pinfunction "PF1/I2C2_SCL/FMC_A1/EVENTOUT_G3") (pintype "bidirectional"))
      (node (ref "U2") (pin "G9") (pinfunction "A1_G9") (pintype "input"))
    )
    (net (code "7") (name "/FMC_A2 {slash} PF2") (class "Default")
      (node (ref "U1") (pin "G1") (pinfunction "PF2/I2C2_SMBA/FMC_A2/EVENTOUT_G1") (pintype "bidirectional"))
      (node (ref "U2") (pin "F7") (pinfunction "A2_F7") (pintype "input"))
    )
    (net (code "8") (name "/FMC_A3 {slash} PF3") (class "Default")
      (node (ref "U1") (pin "H4") (pinfunction "PF3/FMC_A3/EVENTOUT_H4") (pintype "bidirectional"))
      (node (ref "U2") (pin "F3") (pinfunction "A3_F3") (pintype "input"))
    )
    (net (code "9") (name "/FMC_A4 {slash} PF4") (class "Default")
      (node (ref "U1") (pin "J5") (pinfunction "PF4/FMC_A4/EVENTOUT_J5") (pintype "bidirectional"))
      (node (ref "U2") (pin "G1") (pinfunction "A4_G1") (pintype "input"))
    )
    (net (code "10") (name "/FMC_A5 {slash} PF5") (class "Default")
      (node (ref "U1") (pin "J4") (pinfunction "PF5/FMC_A5/EVENTOUT_J4") (pintype "bidirectional"))
      (node (ref "U2") (pin "G2") (pinfunction "A5_G2") (pintype "input"))
    )
    (net (code "11") (name "/FMC_A6 {slash} PF12") (class "Default")
      (node (ref "U1") (pin "R7") (pinfunction "PF12/FMC_A6/EVENTOUT_R7") (pintype "bidirectional"))
      (node (ref "U2") (pin "G3") (pinfunction "A6_G3") (pintype "input"))
    )
    (net (code "12") (name "/FMC_A7 {slash} PF13") (class "Default")
      (node (ref "U1") (pin "P7") (pinfunction "PF13/DFSDM1_DATIN6/I2C4_SMBA/FMC_A7/EVENTOUT_P7") (pintype "bidirectional"))
      (node (ref "U2") (pin "H1") (pinfunction "A7_H1") (pintype "input"))
    )
    (net (code "13") (name "/FMC_A8 {slash} PF14") (class "Default")
      (node (ref "U1") (pin "P8") (pinfunction "PF14/DFSDM1_CKIN6/I2C4_SCL/FMC_A8/EVENTOUT_P8") (pintype "bidirectional"))
      (node (ref "U2") (pin "H2") (pinfunction "A8_H2") (pintype "input"))
    )
    (net (code "14") (name "/FMC_A9 {slash} PF15") (class "Default")
      (node (ref "U1") (pin "R9") (pinfunction "PF15/I2C4_SDA/FMC_A9/EVENTOUT_R9") (pintype "bidirectional"))
      (node (ref "U2") (pin "J3") (pinfunction "A9_J3") (pintype "input"))
    )
    (net (code "15") (name "/FMC_A10 {slash} PG0") (class "Default")
      (node (ref "U1") (pin "T8") (pinfunction "PG0/FMC_A10/EVENTOUT_T8") (pintype "bidirectional"))
      (node (ref "U2") (pin "G7") (pinfunction "A10_G7") (pintype "input"))
    )
    (net (code "16") (name "/FMC_A11 {slash} PG1") (class "Default")
      (node (ref "U1") (pin "U8") (pinfunction "PG1/FMC_A11/EVENTOUT_U8") (pintype "bidirectional"))
      (node (ref "U2") (pin "H9") (pinfunction "A11_H9") (pintype "input"))
    )
    (net (code "17") (name "/FMC_BA0 {slash} PG4") (class "Default")
      (node (ref "U1") (pin "H14") (pinfunction "PG4/TIM1_BKIN2/TIM1_BKIN2_COMP12/FMC_A14/FMC_BA0/EVENTOUT_H14") (pintype "bidirectional"))
      (node (ref "U2") (pin "J7") (pinfunction "BA0_J7") (pintype "input"))
    )
    (net (code "18") (name "/FMC_BA1 {slash} PG5") (class "Default")
      (node (ref "U1") (pin "G14") (pinfunction "PG5/TIM1_ETR/FMC_A15/FMC_BA1/EVENTOUT_G14") (pintype "bidirectional"))
      (node (ref "U2") (pin "H8") (pinfunction "BA1_H8") (pintype "input"))
    )
    (net (code "19") (name "/FMC_D0 {slash} PD14") (class "Default")
      (node (ref "U1") (pin "P16") (pinfunction "PD14/TIM4_CH3/SAI3_MCLK_B/UART8_CTS/FMC_D0/FMC_DA0/EVENTOUT_P16") (pintype "bidirectional"))
      (node (ref "U2") (pin "R8") (pinfunction "DQ0_R8") (pintype "bidirectional"))
    )
    (net (code "20") (name "/FMC_D1 {slash} PD15") (class "Default")
      (node (ref "U1") (pin "P15") (pinfunction "PD15/TIM4_CH4/SAI3_MCLK_A/UART8_RTS/UART8_DE/FMC_D1/FMC_DA1/EVENTOUT_P15") (pintype "bidirectional"))
      (node (ref "U2") (pin "N7") (pinfunction "DQ1_N7") (pintype "bidirectional"))
    )
    (net (code "21") (name "/FMC_D2 {slash} PD0") (class "Default")
      (node (ref "U1") (pin "D13") (pinfunction "PD0/DFSDM1_CKIN6/SAI3_SCK_A/UART4_RX/FDCAN1_RX/FMC_D2/FMC_DA2/EVENTOUT_D13") (pintype "bidirectional"))
      (node (ref "U2") (pin "R9") (pinfunction "DQ2_R9") (pintype "bidirectional"))
    )
    (net (code "22") (name "/FMC_D3 {slash} PD1") (class "Default")
      (node (ref "U1") (pin "E12") (pinfunction "PD1/DFSDM1_DATIN6/SAI3_SD_A/UART4_TX/FDCAN1_TX/FMC_D3/FMC_DA3/EVENTOUT_E12") (pintype "bidirectional"))
      (node (ref "U2") (pin "N8") (pinfunction "DQ3_N8") (pintype "bidirectional"))
    )
    (net (code "23") (name "/FMC_D4 {slash} PE7") (class "Default")
      (node (ref "U1") (pin "U9") (pinfunction "PE7/TIM1_ETR/DFSDM1_DATIN2/UART7_RX/QUADSPI_BK2_IO0/FMC_D4/FMC_DA4/EVENTOUT_U9") (pintype "bidirectional"))
      (node (ref "U2") (pin "P9") (pinfunction "DQ4_P9") (pintype "bidirectional"))
    )
    (net (code "24") (name "/FMC_D5 {slash} PE8") (class "Default")
      (node (ref "U1") (pin "T9") (pinfunction "PE8/TIM1_CH1N/DFSDM1_CKIN2/UART7_TX/QUADSPI_BK2_IO1/FMC_D5/FMC_DA5/COMP2_OUT/EVENTOUT_T9") (pintype "bidirectional"))
      (node (ref "U2") (pin "M8") (pinfunction "DQ5_M8") (pintype "bidirectional"))
    )
    (net (code "25") (name "/FMC_D6 {slash} PE9") (class "Default")
      (node (ref "U1") (pin "P9") (pinfunction "PE9/TIM1_CH1/DFSDM1_CKOUT/UART7_RTS/UART7_DE/QUADSPI_BK2_IO2/FMC_D6/FMC_DA6/EVENTOUT_P9") (pintype "bidirectional"))
      (node (ref "U2") (pin "M7") (pinfunction "DQ6_M7") (pintype "bidirectional"))
    )
    (net (code "26") (name "/FMC_D7 {slash} PE10") (class "Default")
      (node (ref "U1") (pin "N9") (pinfunction "PE10/TIM1_CH2N/DFSDM1_DATIN4/UART7_CTS/QUADSPI_BK2_IO3/FMC_D7/FMC_DA7/EVENTOUT_N9") (pintype "bidirectional"))
      (node (ref "U2") (pin "L8") (pinfunction "DQ7_L8") (pintype "bidirectional"))
    )
    (net (code "27") (name "/FMC_D8 {slash} PE11") (class "Default")
      (node (ref "U1") (pin "P10") (pinfunction "PE11/TIM1_CH2/DFSDM1_CKIN4/SPI4_NSS/SAI2_SD_B/FMC_D8/FMC_DA8/LCD_G3/EVENTOUT_P10") (pintype "bidirectional"))
      (node (ref "U2") (pin "L2") (pinfunction "DQ8_L2") (pintype "bidirectional"))
    )
    (net (code "28") (name "/FMC_D9 {slash} PE12") (class "Default")
      (node (ref "U1") (pin "R10") (pinfunction "PE12/TIM1_CH3N/DFSDM1_DATIN5/SPI4_SCK/SAI2_SCK_B/FMC_D9/FMC_DA9/COMP1_OUT/LCD_B4/EVENTOUT_R10") (pintype "bidirectional"))
      (node (ref "U2") (pin "M3") (pinfunction "DQ9_M3") (pintype "bidirectional"))
    )
    (net (code "29") (name "/FMC_D10 {slash} PE13") (class "Default")
      (node (ref "U1") (pin "T10") (pinfunction "PE13/TIM1_CH3/DFSDM1_CKIN5/SPI4_MISO/SAI2_FS_B/FMC_D10/FMC_DA10/COMP2_OUT/LCD_DE/EVENTOUT_T10") (pintype "bidirectional"))
      (node (ref "U2") (pin "M2") (pinfunction "DQ10_M2") (pintype "bidirectional"))
    )
    (net (code "30") (name "/FMC_D11 {slash} PE14") (class "Default")
      (node (ref "U1") (pin "U10") (pinfunction "PE14/TIM1_CH4/SPI4_MOSI/SAI2_MCLK_B/FMC_D11/FMC_DA11/LCD_CLK/EVENTOUT_U10") (pintype "bidirectional"))
      (node (ref "U2") (pin "P1") (pinfunction "DQ11_P1") (pintype "bidirectional"))
    )
    (net (code "31") (name "/FMC_D12 {slash} PE15") (class "Default")
      (node (ref "U1") (pin "R11") (pinfunction "PE15/TIM1_BKIN/FMC_D12/FMC_DA12/TIM1_BKIN_COMP12/COMP_TIM1_BKIN/LCD_R7/EVENTOUT_R11") (pintype "bidirectional"))
      (node (ref "U2") (pin "N2") (pinfunction "DQ12_N2") (pintype "bidirectional"))
    )
    (net (code "32") (name "/FMC_D13 {slash} PD8") (class "Default")
      (node (ref "U1") (pin "U16") (pinfunction "PD8/DFSDM1_CKIN3/SAI3_SCK_B/USART3_TX/SPDIFRX1_IN2/FMC_D13/FMC_DA13/EVENTOUT_U16") (pintype "bidirectional"))
      (node (ref "U2") (pin "R1") (pinfunction "DQ13_R1") (pintype "bidirectional"))
    )
    (net (code "33") (name "/FMC_D14 {slash} PD9") (class "Default")
      (node (ref "U1") (pin "T17") (pinfunction "PD9/DFSDM1_DATIN3/SAI3_SD_B/USART3_RX/FDCAN2_RXFD_MODE/FMC_D14/FMC_DA14/EVENTOUT_T17") (pintype "bidirectional"))
      (node (ref "U2") (pin "N3") (pinfunction "DQ14_N3") (pintype "bidirectional"))
    )
    (net (code "34") (name "/FMC_D15 {slash} PD10") (class "Default")
      (node (ref "U1") (pin "T16") (pinfunction "PD10/DFSDM1_CKOUT/SAI3_FS_B/USART3_CK/FDCAN2_TXFD_MODE/FMC_D15/FMC_DA15/LCD_B3/EVENTOUT_T16") (pintype "bidirectional"))
      (node (ref "U2") (pin "R2") (pinfunction "DQ15_R2") (pintype "bidirectional"))
    )
    (net (code "35") (name "/FMC_D16 {slash} PH8") (class "Default")
      (node (ref "U1") (pin "T13") (pinfunction "PH8/TIM5_ETR/I2C3_SDA/FMC_D16/DCMI_HSYNC/LCD_R2/EVENTOUT_T13") (pintype "bidirectional"))
      (node (ref "U2") (pin "E8") (pinfunction "DQ16_E8") (pintype "bidirectional"))
    )
    (net (code "36") (name "/FMC_D17 {slash} PH9") (class "Default")
      (node (ref "U1") (pin "R13") (pinfunction "PH9/TIM12_CH2/I2C3_SMBA/FMC_D17/DCMI_D0/LCD_R3/EVENTOUT_R13") (pintype "bidirectional"))
      (node (ref "U2") (pin "D7") (pinfunction "DQ17_D7") (pintype "bidirectional"))
    )
    (net (code "37") (name "/FMC_D18 {slash} PH10") (class "Default")
      (node (ref "U1") (pin "P13") (pinfunction "PH10/TIM5_CH1/I2C4_SMBA/FMC_D18/DCMI_D1/LCD_R4/EVENTOUT_P13") (pintype "bidirectional"))
      (node (ref "U2") (pin "D8") (pinfunction "DQ18_D8") (pintype "bidirectional"))
    )
    (net (code "38") (name "/FMC_D19 {slash} PH11") (class "Default")
      (node (ref "U1") (pin "P14") (pinfunction "PH11/TIM5_CH2/I2C4_SCL/FMC_D19/DCMI_D2/LCD_R5/EVENTOUT_P14") (pintype "bidirectional"))
      (node (ref "U2") (pin "B9") (pinfunction "DQ19_B9") (pintype "bidirectional"))
    )
    (net (code "39") (name "/FMC_D20 {slash} PH12") (class "Default")
      (node (ref "U1") (pin "R14") (pinfunction "PH12/TIM5_CH3/I2C4_SDA/FMC_D20/DCMI_D3/LCD_R6/EVENTOUT_R14") (pintype "bidirectional"))
      (node (ref "U2") (pin "C8") (pinfunction "DQ20_C8") (pintype "bidirectional"))
    )
    (net (code "40") (name "/FMC_D21 {slash} PH13") (class "Default")
      (node (ref "U1") (pin "D16") (pinfunction "PH13/TIM8_CH1N/UART4_TX/FDCAN1_TX/FMC_D21/LCD_G2/EVENTOUT_D16") (pintype "bidirectional"))
      (node (ref "U2") (pin "A9") (pinfunction "DQ21_A9") (pintype "bidirectional"))
    )
    (net (code "41") (name "/FMC_D22 {slash} PH14") (class "Default")
      (node (ref "U1") (pin "B17") (pinfunction "PH14/TIM8_CH2N/UART4_RX/FDCAN1_RX/FMC_D22/DCMI_D4/LCD_G3/EVENTOUT_B17") (pintype "bidirectional"))
      (node (ref "U2") (pin "C7") (pinfunction "DQ22_C7") (pintype "bidirectional"))
    )
    (net (code "42") (name "/FMC_D23 {slash} PH15") (class "Default")
      (node (ref "U1") (pin "B16") (pinfunction "PH15/TIM8_CH3N/FDCAN1_TXFD_MODE/FMC_D23/DCMI_D11/LCD_G4/EVENTOUT_B16") (pintype "bidirectional"))
      (node (ref "U2") (pin "A8") (pinfunction "DQ23_A8") (pintype "bidirectional"))
    )
    (net (code "43") (name "/FMC_D24 {slash} PI0") (class "Default")
      (node (ref "U1") (pin "A16") (pinfunction "PI0/TIM5_CH4/SPI2_NSS/I2S2_WS/FDCAN1_RXFD_MODE/FMC_D24/DCMI_D13/LCD_G5/EVENTOUT_A16") (pintype "bidirectional"))
      (node (ref "U2") (pin "A2") (pinfunction "DQ24_A2") (pintype "bidirectional"))
    )
    (net (code "44") (name "/FMC_D25 {slash} PI1") (class "Default")
      (node (ref "U1") (pin "A15") (pinfunction "PI1/TIM8_BKIN2/SPI2_SCK/I2S2_CK/TIM8_BKIN2_COMP12/FMC_D25/DCMI_D8/LCD_G6/EVENTOUT_A15") (pintype "bidirectional"))
      (node (ref "U2") (pin "C3") (pinfunction "DQ25_C3") (pintype "bidirectional"))
    )
    (net (code "45") (name "/FMC_D26 {slash} PI2") (class "Default")
      (node (ref "U1") (pin "B15") (pinfunction "PI2/TIM8_CH4/SPI2_MISO/I2S2_SDI/FMC_D26/DCMI_D9/LCD_G7/EVENTOUT_B15") (pintype "bidirectional"))
      (node (ref "U2") (pin "A1") (pinfunction "DQ26_A1") (pintype "bidirectional"))
    )
    (net (code "46") (name "/FMC_D27 {slash} PI3") (class "Default")
      (node (ref "U1") (pin "C14") (pinfunction "PI3/TIM8_ETR/SPI2_MOSI/I2S2_SDO/FMC_D27/DCMI_D10/EVENTOUT_C14") (pintype "bidirectional"))
      (node (ref "U2") (pin "C2") (pinfunction "DQ27_C2") (pintype "bidirectional"))
    )
    (net (code "47") (name "/FMC_D28 {slash} PI6") (class "Default")
      (node (ref "U1") (pin "A2") (pinfunction "PI6/TIM8_CH2/SAI2_SD_A/FMC_D28/DCMI_D6/LCD_B6/EVENTOUT_A2") (pintype "bidirectional"))
      (node (ref "U2") (pin "B1") (pinfunction "DQ28_B1") (pintype "bidirectional"))
    )
    (net (code "48") (name "/FMC_D29 {slash} PI7") (class "Default")
      (node (ref "U1") (pin "B3") (pinfunction "PI7/TIM8_CH3/SAI2_FS_A/FMC_D29/DCMI_D7/LCD_B7/EVENTOUT_B3") (pintype "bidirectional"))
      (node (ref "U2") (pin "D2") (pinfunction "DQ29_D2") (pintype "bidirectional"))
    )
    (net (code "49") (name "/FMC_D30 {slash} PI9") (class "Default")
      (node (ref "U1") (pin "E2") (pinfunction "PI9/UART4_RX/FDCAN1_RX/FMC_D30/LCD_VSYNC/EVENTOUT_E2") (pintype "bidirectional"))
      (node (ref "U2") (pin "D3") (pinfunction "DQ30_D3") (pintype "bidirectional"))
    )
    (net (code "50") (name "/FMC_D31 {slash} PI10") (class "Default")
      (node (ref "U1") (pin "F3") (pinfunction "PI10/FDCAN1_RXFD_MODE/ETH_MII_RX_ER/FMC_D31/LCD_HSYNC/EVENTOUT_F3") (pintype "bidirectional"))
      (node (ref "U2") (pin "E2") (pinfunction "DQ31_E2") (pintype "bidirectional"))
    )
    (net (code "51") (name "/FMC_NBL0 {slash} PE0") (class "Default")
      (node (ref "U1") (pin "C4") (pinfunction "PE0/LPTIM1_ETR/TIM4_ETR/HRTIM_SCIN/LPTIM2_ETR/UART8_RX/FDCAN1_RXFD_MODE/SAI2_MCLK_A/FMC_NBL0/DCMI_D2/EVENTOUT_C4") (pintype "bidirectional"))
      (node (ref "U2") (pin "K9") (pinfunction "DQM0_K9") (pintype "bidirectional"))
    )
    (net (code "52") (name "/FMC_NBL1 {slash} PE1") (class "Default")
      (node (ref "U1") (pin "B4") (pinfunction "PE1/LPTIM1_IN2/HRTIM_SCOUT/UART8_TX/FDCAN1_TXFD_MODE/FMC_NBL1/DCMI_D3/EVENTOUT_B4") (pintype "bidirectional"))
      (node (ref "U2") (pin "K1") (pinfunction "DQM1_K1") (pintype "bidirectional"))
    )
    (net (code "53") (name "/FMC_NBL2 {slash} PI4") (class "Default")
      (node (ref "U1") (pin "A4") (pinfunction "PI4/TIM8_BKIN/SAI2_MCLK_A/TIM8_BKIN_COMP12/FMC_NBL2/DCMI_D5/LCD_B4/EVENTOUT_A4") (pintype "bidirectional"))
      (node (ref "U2") (pin "F8") (pinfunction "DQM2_F8") (pintype "bidirectional"))
    )
    (net (code "54") (name "/FMC_NBL3 {slash} PI5") (class "Default")
      (node (ref "U1") (pin "A3") (pinfunction "PI5/TIM8_CH1/SAI2_SCK_A/FMC_NBL3/DCMI_VSYNC/LCD_B5/EVENTOUT_A3") (pintype "bidirectional"))
      (node (ref "U2") (pin "F2") (pinfunction "DQM3_F2") (pintype "bidirectional"))
    )
    (net (code "55") (name "/FMC_SDCKE0 {slash} PH2") (class "Default")
      (node (ref "U1") (pin "N2") (pinfunction "PH2/LPTIM1_IN2/QUADSPI_BK2_IO0/SAI2_SCK_B/ETH_MII_CRS/FMC_SDCKE0/LCD_R0/EVENTOUT_N2") (pintype "bidirectional"))
      (node (ref "U2") (pin "J2") (pinfunction "CKE_J2") (pintype "input"))
    )
    (net (code "56") (name "/FMC_SDCLK {slash} PG8") (class "Default")
      (node (ref "U1") (pin "F15") (pinfunction "PG8/TIM8_ETR/SPI6_NSS/USART6_RTS/USART6_DE/SPDIFRX1_IN3/ETH_PPS_OUT/FMC_SDCLK/LCD_G7/EVENTOUT_F15") (pintype "bidirectional"))
      (node (ref "U2") (pin "J1") (pinfunction "CLK_J1") (pintype "input"))
    )
    (net (code "57") (name "/FMC_SDNCAS {slash} PG15") (class "Default")
      (node (ref "U1") (pin "D6") (pinfunction "PG15/USART6_CTS/USART6_NSS/FMC_SDNCAS/DCMI_D13/EVENTOUT_D6") (pintype "bidirectional"))
      (node (ref "U2") (pin "K7") (pinfunction "CAS#_K7") (pintype "input"))
    )
    (net (code "58") (name "/FMC_SDNE0 {slash} PH3") (class "Default")
      (node (ref "U1") (pin "P2") (pinfunction "PH3/QUADSPI_BK2_IO1/SAI2_MCLK_B/ETH_MII_COL/FMC_SDNE0/LCD_R1/EVENTOUT_P2") (pintype "bidirectional"))
      (node (ref "U2") (pin "J8") (pinfunction "CS#_J8") (pintype "input"))
    )
    (net (code "59") (name "/FMC_SDNRAS {slash} PF11") (class "Default")
      (node (ref "U1") (pin "T7") (pinfunction "PF11/SPI5_MOSI/SAI2_SD_B/FMC_SDNRAS/DCMI_D12/EVENTOUT_T7") (pintype "bidirectional"))
      (node (ref "U2") (pin "J9") (pinfunction "RAS#_J9") (pintype "input"))
    )
    (net (code "60") (name "/FMC_SDNWE {slash} PC0") (class "Default")
      (node (ref "U1") (pin "L2") (pinfunction "PC0/DFSDM1_CKIN0/DFSDM1_DATIN4/SAI2_FS_B/OTG_HS_ULPI_STP/FMC_SDNWE/LCD_R5/EVENTOUT_L2") (pintype "bidirectional"))
      (node (ref "U2") (pin "K8") (pinfunction "WE#_K8") (pintype "input"))
    )
    (net (code "61") (name "/LED {slash} PC13") (class "Default")
      (node (ref "LED3") (pin "2") (pinfunction "K_2") (pintype "passive"))
      (node (ref "U1") (pin "E3") (pinfunction "PC13/EVENTOUT_E3") (pintype "bidirectional"))
      (node (ref "U4") (pin "35") (pinfunction "35_35") (pintype "passive"))
    )
    (net (code "62") (name "/OS_25M_IN") (class "Default")
      (node (ref "C31") (pin "2") (pinfunction "2_2") (pintype "passive"))
      (node (ref "U1") (pin "J2") (pinfunction "PH0-OSC_IN(PH0)/EVENTOUT_J2") (pintype "bidirectional"))
      (node (ref "X1") (pin "3") (pinfunction "3_3") (pintype "passive"))
    )
    (net (code "63") (name "/OS_25M_OUT") (class "Default")
      (node (ref "C30") (pin "2") (pinfunction "2_2") (pintype "passive"))
      (node (ref "U1") (pin "J1") (pinfunction "PH1-OSC_OUT(PH1)/EVENTOUT_J1") (pintype "bidirectional"))
      (node (ref "X1") (pin "1") (pinfunction "1_1") (pintype "passive"))
    )
    (net (code "64") (name "/OS_32K_IN") (class "Default")
      (node (ref "C32") (pin "1") (pinfunction "1_1") (pintype "passive"))
      (node (ref "U1") (pin "C2") (pinfunction "PC14-OSC32_IN/EVENTOUT_C2") (pintype "bidirectional"))
      (node (ref "X2") (pin "2") (pinfunction "2_2") (pintype "passive"))
    )
    (net (code "65") (name "/OS_32K_OUT") (class "Default")
      (node (ref "C33") (pin "1") (pinfunction "1_1") (pintype "passive"))
      (node (ref "U1") (pin "C1") (pinfunction "PC15-OSC32_OUT/EVENTOUT_C1") (pintype "bidirectional"))
      (node (ref "X2") (pin "1") (pinfunction "1_1") (pintype "passive"))
    )
    (net (code "66") (name "/PA0") (class "Default")
      (node (ref "U1") (pin "N5") (pinfunction "PA0/TIM2_CH1/TIM2_ETR/TIM5_CH1/TIM8_ETR/TIM15_BKIN/USART2_CTS/USART2_NSS/UART4_TX/SDMMC2_CMD/SAI2_SD_B/ETH_MII_CRS/EVENTOUT_N5") (pintype "bidirectional"))
      (node (ref "U5") (pin "40") (pinfunction "40_40") (pintype "passive"))
    )
    (net (code "67") (name "/PA0_C") (class "Default")
      (node (ref "U1") (pin "T1") (pinfunction "PA0_C/TIM2_CH1/TIM2_ETR/TIM5_CH1/TIM8_ETR/TIM15_BKIN/USART2_CTS/USART2_NSS/UART4_TX/SDMMC2_CMD/SAI2_SD_B/ETH_MII_CRS/EVENTOUT_T1") (pintype "bidirectional"))
      (node (ref "U5") (pin "57") (pinfunction "57_57") (pintype "passive"))
    )
    (net (code "68") (name "/PA1") (class "Default")
      (node (ref "U1") (pin "N4") (pinfunction "PA1/TIM2_CH2/TIM5_CH2/LPTIM3_OUT/TIM15_CH1N/USART2_RTS/USART2_DE/UART4_RX/QUADSPI_BK1_IO3/SAI2_MCLK_B/ETH_MII_RX_CLK/ETH_RMII_REF_CLK/LCD_R2/EVENTOUT_N4") (pintype "bidirectional"))
      (node (ref "U5") (pin "44") (pinfunction "44_44") (pintype "passive"))
    )
    (net (code "69") (name "/PA1_C") (class "Default")
      (node (ref "U1") (pin "T2") (pinfunction "PA1_C/TIM2_CH2/TIM5_CH2/LPTIM3_OUT/TIM15_CH1N/USART2_RTS/USART2_DE/UART4_RX/QUADSPI_BK1_IO3/SAI2_MCLK_B/ETH_MII_RX_CLK/ETH_RMII_REF_CLK/LCD_R2/EVENTOUT_T2") (pintype "bidirectional"))
      (node (ref "U5") (pin "55") (pinfunction "55_55") (pintype "passive"))
    )
    (net (code "70") (name "/PA2") (class "Default")
      (node (ref "U1") (pin "N3") (pinfunction "PA2/TIM2_CH3/TIM5_CH3/LPTIM4_OUT/TIM15_CH1/USART2_TX/SAI2_SCK_B/ETH_MDIO/MDIOS_MDIO/LCD_R1/EVENTOUT_N3") (pintype "bidirectional"))
      (node (ref "U5") (pin "50") (pinfunction "50_50") (pintype "passive"))
    )
    (net (code "71") (name "/PA3") (class "Default")
      (node (ref "U1") (pin "U2") (pinfunction "PA3/TIM2_CH4/TIM5_CH4/LPTIM5_OUT/TIM15_CH2/USART2_RX/LCD_B2/OTG_HS_ULPI_D0/ETH_MII_COL/LCD_B5/EVENTOUT_U2") (pintype "bidirectional"))
      (node (ref "U5") (pin "53") (pinfunction "53_53") (pintype "passive"))
    )
    (net (code "72") (name "/PA4") (class "Default")
      (node (ref "U1") (pin "U3") (pinfunction "PA4/D1PWREN/TIM5_ETR/SPI1_NSS/I2S1_WS/SPI3_NSS/I2S3_WS/USART2_CK/SPI6_NSS/OTG_HS_SOF/DCMI_HSYNC/LCD_VSYNC/EVENTOUT_U3") (pintype "bidirectional"))
      (node (ref "U5") (pin "47") (pinfunction "47_47") (pintype "passive"))
    )
    (net (code "73") (name "/PA5") (class "Default")
      (node (ref "U1") (pin "T3") (pinfunction "PA5/D2PWREN/TIM2_CH1/TIM2_ETR/TIM8_CH1N/SPI1_SCK/I2S1_CK/SPI6_SCK/OTG_HS_ULPI_CK/LCD_R4/EVENTOUT_T3") (pintype "bidirectional"))
      (node (ref "U5") (pin "49") (pinfunction "49_49") (pintype "passive"))
    )
    (net (code "74") (name "/PA6") (class "Default")
      (node (ref "U1") (pin "R3") (pinfunction "PA6/TIM1_BKIN/TIM3_CH1/TIM8_BKIN/SPI1_MISO/I2S1_SDI/SPI6_MISO/TIM13_CH1/TIM8_BKIN_COMP12/MDIOS_MDC/TIM1_BKIN_COMP12/DCMI_PIXCLK/LCD_G2/EVENTOUT_R3") (pintype "bidirectional"))
      (node (ref "U5") (pin "51") (pinfunction "51_51") (pintype "passive"))
    )
    (net (code "75") (name "/PA7") (class "Default")
      (node (ref "U1") (pin "R5") (pinfunction "PA7/TIM1_CH1N/TIM3_CH2/TIM8_CH1N/SPI1_MOSI/I2S1_SDO/SPI6_MOSI/TIM14_CH1/ETH_MII_RX_DV/ETH_RMII_CRS_DV/FMC_SDNWE/EVENTOUT_R5") (pintype "bidirectional"))
      (node (ref "U5") (pin "41") (pinfunction "41_41") (pintype "passive"))
    )
    (net (code "76") (name "/PA8") (class "Default")
      (node (ref "U1") (pin "E15") (pinfunction "PA8/MCO1/TIM1_CH1/HRTIM_CHB2/TIM8_BKIN2/I2C3_SCL/USART1_CK/OTG_FS_SOF/UART7_RX/TIM8_BKIN2_COMP12/LCD_B3/LCD_R6/EVENTOUT_E15") (pintype "bidirectional"))
      (node (ref "U4") (pin "17") (pinfunction "17_17") (pintype "passive"))
    )
    (net (code "77") (name "/PA9") (class "Default")
      (node (ref "JP1") (pin "7") (pinfunction "7_7") (pintype "passive"))
      (node (ref "U1") (pin "D15") (pinfunction "PA9/TIM1_CH2/HRTIM_CHC1/LPUART1_TX/I2C3_SMBA/SPI2_SCK/I2S2_CK/USART1_TX/FDCAN1_RXFD_MODE/DCMI_D0/LCD_R5/EVENTOUT_D15") (pintype "bidirectional"))
      (node (ref "U4") (pin "19") (pinfunction "19_19") (pintype "passive"))
    )
    (net (code "78") (name "/PA10") (class "Default")
      (node (ref "JP1") (pin "6") (pinfunction "6_6") (pintype "passive"))
      (node (ref "U1") (pin "D14") (pinfunction "PA10/TIM1_CH3/HRTIM_CHC2/LPUART1_RX/USART1_RX/FDCAN1_TXFD_MODE/OTG_FS_ID/MDIOS_MDIO/LCD_B4/DCMI_D1/LCD_B1/EVENTOUT_D14") (pintype "bidirectional"))
      (node (ref "U4") (pin "21") (pinfunction "21_21") (pintype "passive"))
    )
    (net (code "79") (name "/PA11") (class "Default")
      (node (ref "U1") (pin "E17") (pinfunction "PA11/TIM1_CH4/HRTIM_CHD1/LPUART1_CTS/SPI2_NSS/I2S2_WS/UART4_RX/USART1_CTS/USART1_NSS/FDCAN1_RX/OTG_FS_DM/LCD_R4/EVENTOUT_E17") (pintype "bidirectional"))
      (node (ref "U4") (pin "13") (pinfunction "13_13") (pintype "passive"))
    )
    (net (code "80") (name "/PA12") (class "Default")
      (node (ref "U1") (pin "E16") (pinfunction "PA12/TIM1_ETR/HRTIM_CHD2/LPUART1_RTS/LPUART1_DE/SPI2_SCK/I2S2_CK/UART4_TX/USART1_RTS/USART1_DE/SAI2_FS_B/FDCAN1_TX/OTG_FS_DP/LCD_R5/EVENTOUT_E16") (pintype "bidirectional"))
      (node (ref "U4") (pin "15") (pinfunction "15_15") (pintype "passive"))
    )
    (net (code "81") (name "/PA15") (class "Default")
      (node (ref "U1") (pin "A14") (pinfunction "PA15/JTDI/TIM2_CH1/TIM2_ETR/HRTIM_FLT1/CEC/SPI1_NSS/I2S1_WS/SPI3_NSS/I2S3_WS/SPI6_NSS/UART4_RTS/UART4_DE/UART7_TX/EVENTOUT_A14") (pintype "bidirectional"))
      (node (ref "U4") (pin "2") (pinfunction "2_2") (pintype "passive"))
    )
    (net (code "82") (name "/PB0") (class "Default")
      (node (ref "U1") (pin "U5") (pinfunction "PB0/TIM1_CH2N/TIM3_CH3/TIM8_CH2N/DFSDM1_CKOUT/UART4_CTS/LCD_R3/OTG_HS_ULPI_D1/ETH_MII_RXD2/LCD_G1/EVENTOUT_U5") (pintype "bidirectional"))
      (node (ref "U5") (pin "37") (pinfunction "37_37") (pintype "passive"))
    )
    (net (code "83") (name "/PB1") (class "Default")
      (node (ref "U1") (pin "T5") (pinfunction "PB1/TIM1_CH3N/TIM3_CH4/TIM8_CH3N/DFSDM1_DATIN1/LCD_R6/OTG_HS_ULPI_D2/ETH_MII_RXD3/LCD_G0/EVENTOUT_T5") (pintype "bidirectional"))
      (node (ref "U5") (pin "39") (pinfunction "39_39") (pintype "passive"))
    )
    (net (code "84") (name "/PB2") (class "Default")
      (node (ref "U1") (pin "R6") (pinfunction "PB2/RTC_OUT/SAI1_D1/DFSDM1_CKIN1/SAI1_SD_A/SPI3_MOSI/I2S3_SDO/SAI4_SD_A/QUADSPI_CLK/SAI4_D1/EVENTOUT_R6") (pintype "bidirectional"))
      (node (ref "U5") (pin "35") (pinfunction "35_35") (pintype "passive"))
    )
    (net (code "85") (name "/PB3") (class "Default")
      (node (ref "U1") (pin "C6") (pinfunction "PB3/JTDO/TRACESWO/TIM2_CH2/HRTIM_FLT4/SPI1_SCK/I2S1_CK/SPI3_SCK/I2S3_CK/SPI6_SCK/SDMMC2_D2/CRS_SYNC/UART7_RX/EVENTOUT_C6") (pintype "bidirectional"))
      (node (ref "U4") (pin "48") (pinfunction "48_48") (pintype "passive"))
    )
    (net (code "86") (name "/PB4") (class "Default")
      (node (ref "U1") (pin "B7") (pinfunction "PB4/NJTRST/TIM16_BKIN/TIM3_CH1/HRTIM_EEV6/SPI1_MISO/I2S1_SDI/SPI3_MISO/I2S3_SDI/SPI2_NSS/I2S2_WS/SPI6_MISO/SDMMC2_D3/UART7_TX/EVENTOUT_B7") (pintype "bidirectional"))
      (node (ref "U4") (pin "44") (pinfunction "44_44") (pintype "passive"))
    )
    (net (code "87") (name "/PB5") (class "Default")
      (node (ref "U1") (pin "A5") (pinfunction "PB5/TIM17_BKIN/TIM3_CH2/HRTIM_EEV7/I2C1_SMBA/SPI1_MOSI/I2S1_SDO/I2C4_SMBA/SPI3_MOSI/I2S3_SDO/SPI6_MOSI/FDCAN2_RX/OTG_HS_ULPI_D7/ETH_PPS_OUT/FMC_SDCKE1/DCMI_D10/UART5_RX/EVENTOUT_A5") (pintype "bidirectional"))
      (node (ref "U4") (pin "50") (pinfunction "50_50") (pintype "passive"))
    )
    (net (code "88") (name "/PB6") (class "Default")
      (node (ref "U1") (pin "B5") (pinfunction "PB6/TIM16_CH1N/TIM4_CH1/HRTIM_EEV8/I2C1_SCL/CEC/I2C4_SCL/USART1_TX/LPUART1_TX/FDCAN2_TX/QUADSPI_BK1_NCS/DFSDM1_DATIN5/FMC_SDNE1/DCMI_D5/UART5_TX/EVENTOUT_B5") (pintype "bidirectional"))
      (node (ref "U4") (pin "52") (pinfunction "52_52") (pintype "passive"))
    )
    (net (code "89") (name "/PB7") (class "Default")
      (node (ref "U1") (pin "C5") (pinfunction "PB7/TIM17_CH1N/TIM4_CH2/HRTIM_EEV9/I2C1_SDA/I2C4_SDA/USART1_RX/LPUART1_RX/FDCAN2_TXFD_MODE/DFSDM1_CKIN5/FMC_NL/DCMI_VSYNC/EVENTOUT_C5") (pintype "bidirectional"))
      (node (ref "U4") (pin "54") (pinfunction "54_54") (pintype "passive"))
    )
    (net (code "90") (name "/PB8") (class "Default")
      (node (ref "U1") (pin "D5") (pinfunction "PB8/TIM16_CH1/TIM4_CH3/DFSDM1_CKIN7/I2C1_SCL/I2C4_SCL/SDMMC1_CKIN/UART4_RX/FDCAN1_RX/SDMMC2_D4/ETH_MII_TXD3/SDMMC1_D4/DCMI_D6/LCD_B6/EVENTOUT_D5") (pintype "bidirectional"))
      (node (ref "U4") (pin "43") (pinfunction "43_43") (pintype "passive"))
    )
    (net (code "91") (name "/PB9") (class "Default")
      (node (ref "U1") (pin "D4") (pinfunction "PB9/TIM17_CH1/TIM4_CH4/DFSDM1_DATIN7/I2C1_SDA/SPI2_NSS/I2S2_WS/I2C4_SDA/SDMMC1_CDIR/UART4_TX/FDCAN1_TX/SDMMC2_D5/I2C4_SMBA/SDMMC1_D5/DCMI_D7/LCD_B7/EVENTOUT_D4") (pintype "bidirectional"))
      (node (ref "U4") (pin "45") (pinfunction "45_45") (pintype "passive"))
    )
    (net (code "92") (name "/PB10") (class "Default")
      (node (ref "U1") (pin "P11") (pinfunction "PB10/TIM2_CH3/HRTIM_SCOUT/LPTIM2_IN1/I2C2_SCL/SPI2_SCK/I2S2_CK/DFSDM1_DATIN7/USART3_TX/QUADSPI_BK1_NCS/OTG_HS_ULPI_D3/ETH_MII_RX_ER/LCD_G4/EVENTOUT_P11") (pintype "bidirectional"))
      (node (ref "U5") (pin "32") (pinfunction "32_32") (pintype "passive"))
    )
    (net (code "93") (name "/PB11") (class "Default")
      (node (ref "U1") (pin "P12") (pinfunction "PB11/TIM2_CH4/HRTIM_SCIN/LPTIM2_ETR/I2C2_SDA/DFSDM1_CKIN7/USART3_RX/OTG_HS_ULPI_D4/ETH_MII_TX_EN/ETH_RMII_TX_EN/LCD_G5/EVENTOUT_P12") (pintype "bidirectional"))
      (node (ref "U5") (pin "28") (pinfunction "28_28") (pintype "passive"))
    )
    (net (code "94") (name "/PB12") (class "Default")
      (node (ref "U1") (pin "T14") (pinfunction "PB12/TIM1_BKIN/I2C2_SMBA/SPI2_NSS/I2S2_WS/DFSDM1_DATIN1/USART3_CK/FDCAN2_RX/OTG_HS_ULPI_D5/ETH_MII_TXD0/ETH_RMII_TXD0/OTG_HS_ID/TIM1_BKIN_COMP12/UART5_RX/EVENTOUT_T14") (pintype "bidirectional"))
      (node (ref "U5") (pin "21") (pinfunction "21_21") (pintype "passive"))
    )
    (net (code "95") (name "/PB13") (class "Default")
      (node (ref "U1") (pin "U14") (pinfunction "PB13/TIM1_CH1N/LPTIM2_OUT/SPI2_SCK/I2S2_CK/DFSDM1_CKIN1/USART3_CTS/USART3_NSS/FDCAN2_TX/OTG_HS_ULPI_D6/ETH_MII_TXD1/ETH_RMII_TXD1/UART5_TX/EVENTOUT_U14") (pintype "bidirectional"))
      (node (ref "U5") (pin "23") (pinfunction "23_23") (pintype "passive"))
    )
    (net (code "96") (name "/PB14") (class "Default")
      (node (ref "U1") (pin "U15") (pinfunction "PB14/TIM1_CH2N/TIM12_CH1/TIM8_CH2N/USART1_TX/SPI2_MISO/I2S2_SDI/DFSDM1_DATIN2/USART3_RTS/USART3_DE/UART4_RTS/UART4_DE/SDMMC2_D0/OTG_HS_DM/EVENTOUT_U15") (pintype "bidirectional"))
      (node (ref "U5") (pin "19") (pinfunction "19_19") (pintype "passive"))
    )
    (net (code "97") (name "/PB15") (class "Default")
      (node (ref "U1") (pin "T15") (pinfunction "PB15/RTC_REFIN/TIM1_CH3N/TIM12_CH2/TIM8_CH3N/USART1_RX/SPI2_MOSI/I2S2_SDO/DFSDM1_CKIN2/UART4_CTS/SDMMC2_D1/OTG_HS_DP/EVENTOUT_T15") (pintype "bidirectional"))
      (node (ref "U5") (pin "17") (pinfunction "17_17") (pintype "passive"))
    )
    (net (code "98") (name "/PC1") (class "Default")
      (node (ref "U1") (pin "M2") (pinfunction "PC1/TRACED0/SAI1_D1/DFSDM1_DATIN0/DFSDM1_CKIN4/SPI2_MOSI/I2S2_SDO/SAI1_SD_A/SAI4_SD_A/SDMMC2_CK/SAI4_D1/ETH_MDC/MDIOS_MDC/EVENTOUT_M2") (pintype "bidirectional"))
      (node (ref "U5") (pin "56") (pinfunction "56_56") (pintype "passive"))
    )
    (net (code "99") (name "/PC2") (class "Default")
      (node (ref "U1") (pin "M3") (pinfunction "PC2/CDSLEEP/DFSDM1_CKIN1/SPI2_MISO/I2S2_SDI/DFSDM1_CKOUT/OTG_HS_ULPI_DIR/ETH_MII_TXD2/FMC_SDNE0/EVENTOUT_M3") (pintype "bidirectional"))
      (node (ref "U5") (pin "48") (pinfunction "48_48") (pintype "passive"))
    )
    (net (code "100") (name "/PC2_C") (class "Default")
      (node (ref "U1") (pin "R1") (pinfunction "PC2_C/CDSLEEP/DFSDM1_CKIN1/SPI2_MISO/I2S2_SDI/DFSDM1_CKOUT/OTG_HS_ULPI_DIR/ETH_MII_TXD2/FMC_SDNE0/EVENTOUT_R1") (pintype "bidirectional"))
      (node (ref "U5") (pin "58") (pinfunction "58_58") (pintype "passive"))
    )
    (net (code "101") (name "/PC3") (class "Default")
      (node (ref "U1") (pin "M4") (pinfunction "PC3/CSLEEP/DFSDM1_DATIN1/SPI2_MOSI/I2S2_SDO/OTG_HS_ULPI_NXT/ETH_MII_TX_CLK/FMC_SDCKE0/EVENTOUT_M4") (pintype "bidirectional"))
      (node (ref "U5") (pin "34") (pinfunction "34_34") (pintype "passive"))
    )
    (net (code "102") (name "/PC3_C") (class "Default")
      (node (ref "U1") (pin "R2") (pinfunction "PC3_C/CSLEEP/DFSDM1_DATIN1/SPI2_MOSI/I2S2_SDO/OTG_HS_ULPI_NXT/ETH_MII_TX_CLK/FMC_SDCKE0/EVENTOUT_R2") (pintype "bidirectional"))
      (node (ref "U5") (pin "54") (pinfunction "54_54") (pintype "passive"))
    )
    (net (code "103") (name "/PC4") (class "Default")
      (node (ref "U1") (pin "T4") (pinfunction "PC4/DFSDM1_CKIN2/I2S1_MCK/SPDIFRX1_IN3/ETH_MII_RXD0/ETH_RMII_RXD0/FMC_SDNE0/EVENTOUT_T4") (pintype "bidirectional"))
      (node (ref "U5") (pin "45") (pinfunction "45_45") (pintype "passive"))
    )
    (net (code "104") (name "/PC5") (class "Default")
      (node (ref "U1") (pin "U4") (pinfunction "PC5/SAI1_D3/DFSDM1_DATIN2/SPDIFRX1_IN4/SAI4_D3/ETH_MII_RXD1/ETH_RMII_RXD1/FMC_SDCKE0/COMP1_OUT/EVENTOUT_U4") (pintype "bidirectional"))
      (node (ref "U5") (pin "43") (pinfunction "43_43") (pintype "passive"))
    )
    (net (code "105") (name "/PC6") (class "Default")
      (node (ref "U1") (pin "F14") (pinfunction "PC6/HRTIM_CHA1/TIM3_CH1/TIM8_CH1/DFSDM1_CKIN3/I2S2_MCK/USART6_TX/SDMMC1_D0DIR/FMC_NWAIT/SDMMC2_D6/SDMMC1_D6/DCMI_D0/LCD_HSYNC/EVENTOUT_F14") (pintype "bidirectional"))
      (node (ref "U4") (pin "25") (pinfunction "25_25") (pintype "passive"))
    )
    (net (code "106") (name "/PC7") (class "Default")
      (node (ref "U1") (pin "F13") (pinfunction "PC7/TRGIO/HRTIM_CHA2/TIM3_CH2/TIM8_CH2/DFSDM1_DATIN3/I2S3_MCK/USART6_RX/SDMMC1_D123DIR/FMC_NE1/SDMMC2_D7/SWPMI_TX/SDMMC1_D7/DCMI_D1/LCD_G6/EVENTOUT_F13") (pintype "bidirectional"))
      (node (ref "U4") (pin "29") (pinfunction "29_29") (pintype "passive"))
    )
    (net (code "107") (name "/PC8") (class "Default")
      (node (ref "U1") (pin "E13") (pinfunction "PC8/TRACED1/HRTIM_CHB1/TIM3_CH3/TIM8_CH3/USART6_CK/UART5_RTS/UART5_DE/FMC_NE2/FMC_NCE/SWPMI_RX/SDMMC1_D0/DCMI_D2/EVENTOUT_E13") (pintype "bidirectional"))
      (node (ref "U4") (pin "27") (pinfunction "27_27") (pintype "passive"))
    )
    (net (code "108") (name "/PC9") (class "Default")
      (node (ref "U1") (pin "E14") (pinfunction "PC9/MCO2/TIM3_CH4/TIM8_CH4/I2C3_SDA/I2S_CKIN/UART5_CTS/QUADSPI_BK1_IO0/LCD_G3/SWPMI_SUSPEND/SDMMC1_D1/DCMI_D3/LCD_B2/EVENTOUT_E14") (pintype "bidirectional"))
      (node (ref "U4") (pin "23") (pinfunction "23_23") (pintype "passive"))
    )
    (net (code "109") (name "/PC10") (class "Default")
      (node (ref "U1") (pin "A13") (pinfunction "PC10/HRTIM_EEV1/DFSDM1_CKIN5/SPI3_SCK/I2S3_CK/USART3_TX/UART4_TX/QUADSPI_BK1_IO1/SDMMC1_D2/DCMI_D8/LCD_R2/EVENTOUT_A13") (pintype "bidirectional"))
      (node (ref "U4") (pin "8") (pinfunction "8_8") (pintype "passive"))
    )
    (net (code "110") (name "/PC11") (class "Default")
      (node (ref "U1") (pin "B13") (pinfunction "PC11/HRTIM_FLT2/DFSDM1_DATIN5/SPI3_MISO/I2S3_SDI/USART3_RX/UART4_RX/QUADSPI_BK2_NCS/SDMMC1_D3/DCMI_D4/EVENTOUT_B13") (pintype "bidirectional"))
      (node (ref "U4") (pin "6") (pinfunction "6_6") (pintype "passive"))
    )
    (net (code "111") (name "/PC12") (class "Default")
      (node (ref "U1") (pin "C12") (pinfunction "PC12/TRACED3/HRTIM_EEV2/SPI3_MOSI/I2S3_SDO/USART3_CK/UART5_TX/SDMMC1_CK/DCMI_D9/EVENTOUT_C12") (pintype "bidirectional"))
      (node (ref "U4") (pin "10") (pinfunction "10_10") (pintype "passive"))
    )
    (net (code "112") (name "/PD2") (class "Default")
      (node (ref "U1") (pin "D12") (pinfunction "PD2/TRACED2/TIM3_ETR/UART5_RX/SDMMC1_CMD/DCMI_D11/EVENTOUT_D12") (pintype "bidirectional"))
      (node (ref "U4") (pin "4") (pinfunction "4_4") (pintype "passive"))
    )
    (net (code "113") (name "/PD3") (class "Default")
      (node (ref "U1") (pin "B12") (pinfunction "PD3/DFSDM1_CKOUT/SPI2_SCK/I2S2_CK/USART2_CTS/USART2_NSS/FMC_CLK/DCMI_D5/LCD_G7/EVENTOUT_B12") (pintype "bidirectional"))
      (node (ref "U4") (pin "12") (pinfunction "12_12") (pintype "passive"))
    )
    (net (code "114") (name "/PD4") (class "Default")
      (node (ref "U1") (pin "A12") (pinfunction "PD4/HRTIM_FLT3/SAI3_FS_A/USART2_RTS/USART2_DE/FDCAN1_RXFD_MODE/FMC_NOE/EVENTOUT_A12") (pintype "bidirectional"))
      (node (ref "U4") (pin "14") (pinfunction "14_14") (pintype "passive"))
    )
    (net (code "115") (name "/PD5") (class "Default")
      (node (ref "U1") (pin "A11") (pinfunction "PD5/HRTIM_EEV3/USART2_TX/FDCAN1_TXFD_MODE/FMC_NWE/EVENTOUT_A11") (pintype "bidirectional"))
      (node (ref "U4") (pin "20") (pinfunction "20_20") (pintype "passive"))
    )
    (net (code "116") (name "/PD6") (class "Default")
      (node (ref "U1") (pin "B11") (pinfunction "PD6/SAI1_D1/DFSDM1_CKIN4/DFSDM1_DATIN1/SPI3_MOSI/I2S3_SDO/SAI1_SD_A/USART2_RX/SAI4_SD_A/FDCAN2_RXFD_MODE/SAI4_D1/SDMMC2_CK/FMC_NWAIT/DCMI_D10/LCD_B2/EVENTOUT_B11") (pintype "bidirectional"))
      (node (ref "U4") (pin "22") (pinfunction "22_22") (pintype "passive"))
    )
    (net (code "117") (name "/PD7") (class "Default")
      (node (ref "U1") (pin "C11") (pinfunction "PD7/DFSDM1_DATIN4/SPI1_MOSI/I2S1_SDO/DFSDM1_CKIN1/USART2_CK/SPDIFRX1_IN1/SDMMC2_CMD/FMC_NE1/EVENTOUT_C11") (pintype "bidirectional"))
      (node (ref "U4") (pin "18") (pinfunction "18_18") (pintype "passive"))
    )
    (net (code "118") (name "/PD11") (class "Default")
      (node (ref "U1") (pin "R15") (pinfunction "PD11/LPTIM2_IN2/I2C4_SMBA/USART3_CTS/USART3_NSS/QUADSPI_BK1_IO0/SAI2_SD_A/FMC_A16/EVENTOUT_R15") (pintype "bidirectional"))
      (node (ref "U5") (pin "15") (pinfunction "15_15") (pintype "passive"))
    )
    (net (code "119") (name "/PD12") (class "Default")
      (node (ref "U1") (pin "R16") (pinfunction "PD12/LPTIM1_IN1/TIM4_CH1/LPTIM2_IN1/I2C4_SCL/USART3_RTS/USART3_DE/QUADSPI_BK1_IO1/SAI2_FS_A/FMC_A17/EVENTOUT_R16") (pintype "bidirectional"))
      (node (ref "U5") (pin "13") (pinfunction "13_13") (pintype "passive"))
    )
    (net (code "120") (name "/PD13") (class "Default")
      (node (ref "U1") (pin "R17") (pinfunction "PD13/LPTIM1_OUT/TIM4_CH2/I2C4_SDA/QUADSPI_BK1_IO3/SAI2_SCK_A/FMC_A18/EVENTOUT_R17") (pintype "bidirectional"))
      (node (ref "U5") (pin "18") (pinfunction "18_18") (pintype "passive"))
    )
    (net (code "121") (name "/PE2") (class "Default")
      (node (ref "U1") (pin "C3") (pinfunction "PE2/TRACECLK/SAI1_CK1/SPI4_SCK/SAI1_MCLK_A/SAI4_MCLK_A/QUADSPI_BK1_IO2/SAI4_CK1/ETH_MII_TXD3/FMC_A23/EVENTOUT_C3") (pintype "bidirectional"))
      (node (ref "U4") (pin "58") (pinfunction "58_58") (pintype "passive"))
    )
    (net (code "122") (name "/PE3") (class "Default")
      (node (ref "U1") (pin "D3") (pinfunction "PE3/TRACED0/TIM15_BKIN/SAI1_SD_B/SAI4_SD_B/FMC_A19/EVENTOUT_D3") (pintype "bidirectional"))
      (node (ref "U4") (pin "56") (pinfunction "56_56") (pintype "passive"))
    )
    (net (code "123") (name "/PE4") (class "Default")
      (node (ref "U1") (pin "D2") (pinfunction "PE4/TRACED1/SAI1_D2/DFSDM1_DATIN3/TIM15_CH1N/SPI4_NSS/SAI1_FS_A/SAI4_FS_A/SAI4_D2/FMC_A20/DCMI_D4/LCD_B0/EVENTOUT_D2") (pintype "bidirectional"))
      (node (ref "U4") (pin "49") (pinfunction "49_49") (pintype "passive"))
    )
    (net (code "124") (name "/PE5") (class "Default")
      (node (ref "U1") (pin "D1") (pinfunction "PE5/TRACED2/SAI1_CK2/DFSDM1_CKIN3/TIM15_CH1/SPI4_MISO/SAI1_SCK_A/SAI4_SCK_A/SAI4_CK2/FMC_A21/DCMI_D6/LCD_G0/EVENTOUT_D1") (pintype "bidirectional"))
      (node (ref "U4") (pin "51") (pinfunction "51_51") (pintype "passive"))
    )
    (net (code "125") (name "/PE6") (class "Default")
      (node (ref "U1") (pin "E5") (pinfunction "PE6/TRACED3/TIM1_BKIN2/SAI1_D1/TIM15_CH2/SPI4_MOSI/SAI1_SD_A/SAI4_SD_A/SAI4_D1/SAI2_MCLK_B/TIM1_BKIN2_COMP12/FMC_A22/DCMI_D7/LCD_G1/EVENTOUT_E5") (pintype "bidirectional"))
      (node (ref "U4") (pin "41") (pinfunction "41_41") (pintype "passive"))
    )
    (net (code "126") (name "/PG2") (class "Default")
      (node (ref "U1") (pin "H16") (pinfunction "PG2/TIM8_BKIN/TIM8_BKIN_COMP12/FMC_A12/EVENTOUT_H16") (pintype "bidirectional"))
      (node (ref "U4") (pin "9") (pinfunction "9_9") (pintype "passive"))
    )
    (net (code "127") (name "/PG3") (class "Default")
      (node (ref "U1") (pin "H15") (pinfunction "PG3/TIM8_BKIN2/TIM8_BKIN2_COMP12/FMC_A13/EVENTOUT_H15") (pintype "bidirectional"))
      (node (ref "U5") (pin "8") (pinfunction "8_8") (pintype "passive"))
    )
    (net (code "128") (name "/PG7") (class "Default")
      (node (ref "U1") (pin "F16") (pinfunction "PG7/HRTIM_CHE2/SAI1_MCLK_A/USART6_CK/FMC_INT/DCMI_D13/LCD_CLK/EVENTOUT_F16") (pintype "bidirectional"))
      (node (ref "U4") (pin "11") (pinfunction "11_11") (pintype "passive"))
    )
    (net (code "129") (name "/PG9") (class "Default")
      (node (ref "U1") (pin "A10") (pinfunction "PG9/SPI1_MISO/I2S1_SDI/USART6_RX/SPDIFRX1_IN4/QUADSPI_BK2_IO2/SAI2_FS_B/FMC_NE2/FMC_NCE/DCMI_VSYNC/EVENTOUT_A10") (pintype "bidirectional"))
      (node (ref "U4") (pin "26") (pinfunction "26_26") (pintype "passive"))
    )
    (net (code "130") (name "/PG10") (class "Default")
      (node (ref "U1") (pin "A9") (pinfunction "PG10/HRTIM_FLT5/SPI1_NSS/I2S1_WS/LCD_G3/SAI2_SD_B/FMC_NE3/DCMI_D2/LCD_B2/EVENTOUT_A9") (pintype "bidirectional"))
      (node (ref "U4") (pin "32") (pinfunction "32_32") (pintype "passive"))
    )
    (net (code "131") (name "/PG11") (class "Default")
      (node (ref "U1") (pin "B9") (pinfunction "PG11/LPTIM1_IN2/HRTIM_EEV4/SPI1_SCK/I2S1_CK/SPDIFRX1_IN1/SDMMC2_D2/ETH_MII_TX_EN/ETH_RMII_TX_EN/DCMI_D3/LCD_B3/EVENTOUT_B9") (pintype "bidirectional"))
      (node (ref "U4") (pin "34") (pinfunction "34_34") (pintype "passive"))
    )
    (net (code "132") (name "/PG12") (class "Default")
      (node (ref "U1") (pin "C9") (pinfunction "PG12/LPTIM1_IN1/HRTIM_EEV5/SPI6_MISO/USART6_RTS/USART6_DE/SPDIFRX1_IN2/LCD_B4/ETH_MII_TXD1/ETH_RMII_TXD1/FMC_NE4/LCD_B1/EVENTOUT_C9") (pintype "bidirectional"))
      (node (ref "U4") (pin "36") (pinfunction "36_36") (pintype "passive"))
    )
    (net (code "133") (name "/PG13") (class "Default")
      (node (ref "U1") (pin "D9") (pinfunction "PG13/TRACED0/LPTIM1_OUT/HRTIM_EEV10/SPI6_SCK/USART6_CTS/USART6_NSS/ETH_MII_TXD0/ETH_RMII_TXD0/FMC_A24/LCD_R0/EVENTOUT_D9") (pintype "bidirectional"))
      (node (ref "U4") (pin "30") (pinfunction "30_30") (pintype "passive"))
    )
    (net (code "134") (name "/PG14") (class "Default")
      (node (ref "U1") (pin "D8") (pinfunction "PG14/TRACED1/LPTIM1_ETR/SPI6_MOSI/USART6_TX/QUADSPI_BK2_IO3/ETH_MII_TXD1/ETH_RMII_TXD1/FMC_A25/LCD_B0/EVENTOUT_D8") (pintype "bidirectional"))
      (node (ref "U4") (pin "28") (pinfunction "28_28") (pintype "passive"))
    )
    (net (code "135") (name "/PH4") (class "Default")
      (node (ref "U1") (pin "P3") (pinfunction "PH4/I2C2_SCL/LCD_G5/OTG_HS_ULPI_NXT/LCD_G4/EVENTOUT_P3") (pintype "bidirectional"))
      (node (ref "U5") (pin "52") (pinfunction "52_52") (pintype "passive"))
    )
    (net (code "136") (name "/PH5") (class "Default")
      (node (ref "U1") (pin "P4") (pinfunction "PH5/I2C2_SDA/SPI5_NSS/FMC_SDNWE/EVENTOUT_P4") (pintype "bidirectional"))
      (node (ref "U5") (pin "46") (pinfunction "46_46") (pintype "passive"))
    )
    (net (code "137") (name "/PH6") (class "Default")
      (node (ref "U1") (pin "T11") (pinfunction "PH6/TIM12_CH1/I2C2_SMBA/SPI5_SCK/ETH_MII_RXD2/FMC_SDNE1/DCMI_D8/EVENTOUT_T11") (pintype "bidirectional"))
      (node (ref "U5") (pin "27") (pinfunction "27_27") (pintype "passive"))
    )
    (net (code "138") (name "/PH7") (class "Default")
      (node (ref "U1") (pin "U13") (pinfunction "PH7/I2C3_SCL/SPI5_MISO/ETH_MII_RXD3/FMC_SDCKE1/DCMI_D9/EVENTOUT_U13") (pintype "bidirectional"))
      (node (ref "U5") (pin "25") (pinfunction "25_25") (pintype "passive"))
    )
    (net (code "139") (name "/PI8") (class "Default")
      (node (ref "U1") (pin "E4") (pinfunction "PI8/EVENTOUT_E4") (pintype "bidirectional"))
      (node (ref "U4") (pin "39") (pinfunction "39_39") (pintype "passive"))
    )
    (net (code "140") (name "/PI11") (class "Default")
      (node (ref "U1") (pin "F4") (pinfunction "PI11/LCD_G6/OTG_HS_ULPI_DIR/EVENTOUT_F4") (pintype "bidirectional"))
      (node (ref "U4") (pin "37") (pinfunction "37_37") (pintype "passive"))
    )
    (net (code "141") (name "/PI12") (class "Default")
      (node (ref "U1") (pin "H1") (pinfunction "PI12/LCD_HSYNC/EVENTOUT_H1") (pintype "bidirectional"))
      (node (ref "U4") (pin "53") (pinfunction "53_53") (pintype "passive"))
    )
    (net (code "142") (name "/PI13") (class "Default")
      (node (ref "U1") (pin "H2") (pinfunction "PI13/LCD_VSYNC/EVENTOUT_H2") (pintype "bidirectional"))
      (node (ref "U4") (pin "55") (pinfunction "55_55") (pintype "passive"))
    )
    (net (code "143") (name "/PI14") (class "Default")
      (node (ref "U1") (pin "H3") (pinfunction "PI14/LCD_CLK/EVENTOUT_H3") (pintype "bidirectional"))
      (node (ref "U4") (pin "57") (pinfunction "57_57") (pintype "passive"))
    )
    (net (code "144") (name "/PI15") (class "Default")
      (node (ref "U1") (pin "P5") (pinfunction "PI15/LCD_G2/LCD_R0/EVENTOUT_P5") (pintype "bidirectional"))
      (node (ref "U5") (pin "42") (pinfunction "42_42") (pintype "passive"))
    )
    (net (code "145") (name "/PJ0") (class "Default")
      (node (ref "U1") (pin "N6") (pinfunction "PJ0/LCD_R7/LCD_R1/EVENTOUT_N6") (pintype "bidirectional"))
      (node (ref "U5") (pin "38") (pinfunction "38_38") (pintype "passive"))
    )
    (net (code "146") (name "/PJ1") (class "Default")
      (node (ref "U1") (pin "P6") (pinfunction "PJ1/LCD_R2/EVENTOUT_P6") (pintype "bidirectional"))
      (node (ref "U5") (pin "36") (pinfunction "36_36") (pintype "passive"))
    )
    (net (code "147") (name "/PJ2") (class "Default")
      (node (ref "U1") (pin "T6") (pinfunction "PJ2/LCD_R3/EVENTOUT_T6") (pintype "bidirectional"))
      (node (ref "U5") (pin "33") (pinfunction "33_33") (pintype "passive"))
    )
    (net (code "148") (name "/PJ3") (class "Default")
      (node (ref "U1") (pin "U6") (pinfunction "PJ3/LCD_R4/EVENTOUT_U6") (pintype "bidirectional"))
      (node (ref "U5") (pin "31") (pinfunction "31_31") (pintype "passive"))
    )
    (net (code "149") (name "/PJ4") (class "Default")
      (node (ref "U1") (pin "U7") (pinfunction "PJ4/LCD_R5/EVENTOUT_U7") (pintype "bidirectional"))
      (node (ref "U5") (pin "29") (pinfunction "29_29") (pintype "passive"))
    )
    (net (code "150") (name "/PJ5") (class "Default")
      (node (ref "U1") (pin "R12") (pinfunction "PJ5/LCD_R6/EVENTOUT_R12") (pintype "bidirectional"))
      (node (ref "U5") (pin "30") (pinfunction "30_30") (pintype "passive"))
    )
    (net (code "151") (name "/PJ6") (class "Default")
      (node (ref "U1") (pin "N15") (pinfunction "PJ6/TIM8_CH2/LCD_R7/EVENTOUT_N15") (pintype "bidirectional"))
      (node (ref "U5") (pin "22") (pinfunction "22_22") (pintype "passive"))
    )
    (net (code "152") (name "/PJ7") (class "Default")
      (node (ref "U1") (pin "N14") (pinfunction "PJ7/TRGIN/TIM8_CH2N/LCD_G0/EVENTOUT_N14") (pintype "bidirectional"))
      (node (ref "U5") (pin "24") (pinfunction "24_24") (pintype "passive"))
    )
    (net (code "153") (name "/PJ8") (class "Default")
      (node (ref "U1") (pin "N13") (pinfunction "PJ8/TIM1_CH3N/TIM8_CH1/UART8_TX/LCD_G1/EVENTOUT_N13") (pintype "bidirectional"))
      (node (ref "U5") (pin "26") (pinfunction "26_26") (pintype "passive"))
    )
    (net (code "154") (name "/PJ9") (class "Default")
      (node (ref "U1") (pin "M14") (pinfunction "PJ9/TIM1_CH3/TIM8_CH1N/UART8_RX/LCD_G2/EVENTOUT_M14") (pintype "bidirectional"))
      (node (ref "U5") (pin "20") (pinfunction "20_20") (pintype "passive"))
    )
    (net (code "155") (name "/PJ10") (class "Default")
      (node (ref "U1") (pin "L14") (pinfunction "PJ10/TIM1_CH2N/TIM8_CH2/SPI5_MOSI/LCD_G3/EVENTOUT_L14") (pintype "bidirectional"))
      (node (ref "U5") (pin "16") (pinfunction "16_16") (pintype "passive"))
    )
    (net (code "156") (name "/PJ11") (class "Default")
      (node (ref "U1") (pin "K14") (pinfunction "PJ11/TIM1_CH2/TIM8_CH2N/SPI5_MISO/LCD_G4/EVENTOUT_K14") (pintype "bidirectional"))
      (node (ref "U5") (pin "14") (pinfunction "14_14") (pintype "passive"))
    )
    (net (code "157") (name "/PJ12") (class "Default")
      (node (ref "U1") (pin "D11") (pinfunction "PJ12/TRGOUT/LCD_G3/LCD_B0/EVENTOUT_D11") (pintype "bidirectional"))
      (node (ref "U4") (pin "16") (pinfunction "16_16") (pintype "passive"))
    )
    (net (code "158") (name "/PJ13") (class "Default")
      (node (ref "U1") (pin "E10") (pinfunction "PJ13/LCD_B4/LCD_B1/EVENTOUT_E10") (pintype "bidirectional"))
      (node (ref "U4") (pin "31") (pinfunction "31_31") (pintype "passive"))
    )
    (net (code "159") (name "/PJ14") (class "Default")
      (node (ref "U1") (pin "D10") (pinfunction "PJ14/LCD_B2/EVENTOUT_D10") (pintype "bidirectional"))
      (node (ref "U4") (pin "33") (pinfunction "33_33") (pintype "passive"))
    )
    (net (code "160") (name "/PJ15") (class "Default")
      (node (ref "U1") (pin "B10") (pinfunction "PJ15/LCD_B3/EVENTOUT_B10") (pintype "bidirectional"))
      (node (ref "U4") (pin "24") (pinfunction "24_24") (pintype "passive"))
    )
    (net (code "161") (name "/PK0") (class "Default")
      (node (ref "U1") (pin "J14") (pinfunction "PK0/TIM1_CH1N/TIM8_CH3/SPI5_SCK/LCD_G5/EVENTOUT_J14") (pintype "bidirectional"))
      (node (ref "U5") (pin "12") (pinfunction "12_12") (pintype "passive"))
    )
    (net (code "162") (name "/PK1") (class "Default")
      (node (ref "U1") (pin "J15") (pinfunction "PK1/TIM1_CH1/TIM8_CH3N/SPI5_NSS/LCD_G6/EVENTOUT_J15") (pintype "bidirectional"))
      (node (ref "U5") (pin "10") (pinfunction "10_10") (pintype "passive"))
    )
    (net (code "163") (name "/PK2") (class "Default")
      (node (ref "U1") (pin "H17") (pinfunction "PK2/TIM1_BKIN/TIM8_BKIN/TIM8_BKIN_COMP12/TIM1_BKIN_COMP12/LCD_G7/EVENTOUT_H17") (pintype "bidirectional"))
      (node (ref "U5") (pin "6") (pinfunction "6_6") (pintype "passive"))
    )
    (net (code "164") (name "/PK3") (class "Default")
      (node (ref "U1") (pin "C8") (pinfunction "PK3/LCD_B4/EVENTOUT_C8") (pintype "bidirectional"))
      (node (ref "U4") (pin "42") (pinfunction "42_42") (pintype "passive"))
    )
    (net (code "165") (name "/PK4") (class "Default")
      (node (ref "U1") (pin "B8") (pinfunction "PK4/LCD_B5/EVENTOUT_B8") (pintype "bidirectional"))
      (node (ref "U4") (pin "40") (pinfunction "40_40") (pintype "passive"))
    )
    (net (code "166") (name "/PK5") (class "Default")
      (node (ref "U1") (pin "A8") (pinfunction "PK5/LCD_B6/EVENTOUT_A8") (pintype "bidirectional"))
      (node (ref "U4") (pin "38") (pinfunction "38_38") (pintype "passive"))
    )
    (net (code "167") (name "/PK6") (class "Default")
      (node (ref "U1") (pin "C7") (pinfunction "PK6/LCD_B7/EVENTOUT_C7") (pintype "bidirectional"))
      (node (ref "U4") (pin "46") (pinfunction "46_46") (pintype "passive"))
    )
    (net (code "168") (name "/PK7") (class "Default")
      (node (ref "U1") (pin "D7") (pinfunction "PK7/LCD_DE/EVENTOUT_D7") (pintype "bidirectional"))
      (node (ref "U4") (pin "47") (pinfunction "47_47") (pintype "passive"))
    )
    (net (code "169") (name "/QSPI_BK1_IO0 {slash} PF8") (class "Default")
      (node (ref "U1") (pin "K4") (pinfunction "PF8/TIM16_CH1N/SPI5_MISO/SAI1_SCK_B/UART7_RTS/UART7_DE/SAI4_SCK_B/TIM13_CH1/QUADSPI_BK1_IO0/EVENTOUT_K4") (pintype "bidirectional"))
      (node (ref "U3") (pin "5") (pinfunction "DI(IO0)_5") (pintype "passive"))
    )
    (net (code "170") (name "/QSPI_BK1_IO1 {slash} PF9") (class "Default")
      (node (ref "U1") (pin "L4") (pinfunction "PF9/TIM17_CH1N/SPI5_MOSI/SAI1_FS_B/UART7_CTS/SAI4_FS_B/TIM14_CH1/QUADSPI_BK1_IO1/EVENTOUT_L4") (pintype "bidirectional"))
      (node (ref "U3") (pin "2") (pinfunction "DO(IO1)_2") (pintype "passive"))
    )
    (net (code "171") (name "/QSPI_BK1_IO2 {slash} PF7") (class "Default")
      (node (ref "U1") (pin "K3") (pinfunction "PF7/TIM17_CH1/SPI5_SCK/SAI1_MCLK_B/UART7_TX/SAI4_MCLK_B/QUADSPI_BK1_IO2/EVENTOUT_K3") (pintype "bidirectional"))
      (node (ref "U3") (pin "3") (pinfunction "WP#(IO2)_3") (pintype "passive"))
    )
    (net (code "172") (name "/QSPI_BK1_IO3 {slash} PF6") (class "Default")
      (node (ref "U1") (pin "K2") (pinfunction "PF6/TIM16_CH1/SPI5_NSS/SAI1_SD_B/UART7_RX/SAI4_SD_B/QUADSPI_BK1_IO3/EVENTOUT_K2") (pintype "bidirectional"))
      (node (ref "U3") (pin "7") (pinfunction "HOLDor#/RESET#(IO3)_7") (pintype "passive"))
    )
    (net (code "173") (name "/QSPI_BK1_NCS {slash} PG6") (class "Default")
      (node (ref "U1") (pin "G15") (pinfunction "PG6/TIM17_BKIN/HRTIM_CHE1/QUADSPI_BK1_NCS/FMC_NE3/DCMI_D12/LCD_R7/EVENTOUT_G15") (pintype "bidirectional"))
      (node (ref "U3") (pin "1") (pinfunction "CS#_1") (pintype "passive"))
    )
    (net (code "174") (name "/QSPI_CLK {slash} PF10") (class "Default")
      (node (ref "U1") (pin "L3") (pinfunction "PF10/TIM16_BKIN/SAI1_D3/QUADSPI_CLK/SAI4_D3/DCMI_D11/LCD_DE/EVENTOUT_L3") (pintype "bidirectional"))
      (node (ref "U3") (pin "6") (pinfunction "CLK_6") (pintype "passive"))
    )
    (net (code "175") (name "/RST") (class "Default")
      (node (ref "C28") (pin "1") (pinfunction "1_1") (pintype "passive"))
      (node (ref "Q1") (pin "3") (pinfunction "C_3") (pintype "passive"))
      (node (ref "R2") (pin "1") (pinfunction "1_1") (pintype "passive"))
      (node (ref "SW2") (pin "1") (pinfunction "1_1") (pintype "passive"))
      (node (ref "U1") (pin "K1") (pinfunction "NRST_K1") (pintype "bidirectional"))
      (node (ref "U4") (pin "3") (pinfunction "3_3") (pintype "passive"))
    )
    (net (code "176") (name "/SWCLK {slash} PA14") (class "Default")
      (node (ref "JP1") (pin "4") (pinfunction "4_4") (pintype "passive"))
      (node (ref "U1") (pin "B14") (pinfunction "PA14/JTCK-SWCLK/EVENTOUT_B14") (pintype "bidirectional"))
      (node (ref "U4") (pin "7") (pinfunction "7_7") (pintype "passive"))
    )
    (net (code "177") (name "/SWDIO {slash} PA13") (class "Default")
      (node (ref "JP1") (pin "5") (pinfunction "5_5") (pintype "passive"))
      (node (ref "U1") (pin "C15") (pinfunction "PA13/JTMS-SWDIO/EVENTOUT_C15") (pintype "bidirectional"))
      (node (ref "U4") (pin "5") (pinfunction "5_5") (pintype "passive"))
    )
    (net (code "178") (name "/VBAT") (class "Default")
      (node (ref "C39") (pin "1") (pinfunction "1_1") (pintype "passive"))
      (node (ref "D2") (pin "3") (pinfunction "3_3") (pintype "passive"))
      (node (ref "U1") (pin "B1") (pinfunction "VBAT_B1") (pintype "power_in"))
    )
    (net (code "179") (name "/VBAT-EXT") (class "Default")
      (node (ref "D2") (pin "1") (pinfunction "1_1") (pintype "passive"))
      (node (ref "U5") (pin "60") (pinfunction "60_60") (pintype "passive"))
    )
    (net (code "180") (name "/VDDA") (class "Default")
      (node (ref "C35") (pin "2") (pinfunction "2_2") (pintype "passive"))
      (node (ref "C36") (pin "2") (pinfunction "2_2") (pintype "passive"))
      (node (ref "FB1") (pin "2") (pinfunction "2_2") (pintype "passive"))
      (node (ref "R8") (pin "1") (pinfunction "1_1") (pintype "passive"))
      (node (ref "U1") (pin "L1") (pinfunction "VDDA_L1") (pintype "power_in"))
    )
    (net (code "181") (name "/VREF") (class "Default")
      (node (ref "C37") (pin "2") (pinfunction "2_2") (pintype "passive"))
      (node (ref "C38") (pin "2") (pinfunction "2_2") (pintype "passive"))
      (node (ref "R8") (pin "2") (pinfunction "2_2") (pintype "passive"))
      (node (ref "U1") (pin "M1") (pinfunction "VREF+_M1") (pintype "input"))
      (node (ref "U5") (pin "59") (pinfunction "59_59") (pintype "passive"))
    )
    (net (code "182") (name "GND") (class "Default")
      (node (ref "C1") (pin "1") (pinfunction "1_1") (pintype "passive"))
      (node (ref "C10") (pin "1") (pinfunction "1_1") (pintype "passive"))
      (node (ref "C11") (pin "1") (pinfunction "1_1") (pintype "passive"))
      (node (ref "C12") (pin "1") (pinfunction "1_1") (pintype "passive"))
      (node (ref "C13") (pin "1") (pinfunction "1_1") (pintype "passive"))
      (node (ref "C14") (pin "1") (pinfunction "1_1") (pintype "passive"))
      (node (ref "C15") (pin "1") (pinfunction "1_1") (pintype "passive"))
      (node (ref "C16") (pin "1") (pinfunction "1_1") (pintype "passive"))
      (node (ref "C17") (pin "1") (pinfunction "1_1") (pintype "passive"))
      (node (ref "C18") (pin "1") (pinfunction "1_1") (pintype "passive"))
      (node (ref "C19") (pin "1") (pinfunction "1_1") (pintype "passive"))
      (node (ref "C2") (pin "1") (pinfunction "1_1") (pintype "passive"))
      (node (ref "C20") (pin "1") (pinfunction "1_1") (pintype "passive"))
      (node (ref "C21") (pin "1") (pinfunction "1_1") (pintype "passive"))
      (node (ref "C22") (pin "1") (pinfunction "1_1") (pintype "passive"))
      (node (ref "C23") (pin "1") (pinfunction "1_1") (pintype "passive"))
      (node (ref "C24") (pin "1") (pinfunction "1_1") (pintype "passive"))
      (node (ref "C25") (pin "1") (pinfunction "1_1") (pintype "passive"))
      (node (ref "C26") (pin "1") (pinfunction "1_1") (pintype "passive"))
      (node (ref "C27") (pin "1") (pinfunction "1_1") (pintype "passive"))
      (node (ref "C28") (pin "2") (pinfunction "2_2") (pintype "passive"))
      (node (ref "C29") (pin "2") (pinfunction "2_2") (pintype "passive"))
      (node (ref "C3") (pin "1") (pinfunction "1_1") (pintype "passive"))
      (node (ref "C30") (pin "1") (pinfunction "1_1") (pintype "passive"))
      (node (ref "C31") (pin "1") (pinfunction "1_1") (pintype "passive"))
      (node (ref "C32") (pin "2") (pinfunction "2_2") (pintype "passive"))
      (node (ref "C33") (pin "2") (pinfunction "2_2") (pintype "passive"))
      (node (ref "C34") (pin "2") (pinfunction "2_2") (pintype "passive"))
      (node (ref "C35") (pin "1") (pinfunction "1_1") (pintype "passive"))
      (node (ref "C36") (pin "1") (pinfunction "1_1") (pintype "passive"))
      (node (ref "C37") (pin "1") (pinfunction "1_1") (pintype "passive"))
      (node (ref "C38") (pin "1") (pinfunction "1_1") (pintype "passive"))
      (node (ref "C39") (pin "2") (pinfunction "2_2") (pintype "passive"))
      (node (ref "C4") (pin "2") (pinfunction "2_2") (pintype "passive"))
      (node (ref "C40") (pin "1") (pinfunction "1_1") (pintype "passive"))
      (node (ref "C43") (pin "1") (pinfunction "1_1") (pintype "passive"))
      (node (ref "C44") (pin "1") (pinfunction "1_1") (pintype "passive"))
      (node (ref "C45") (pin "1") (pinfunction "1_1") (pintype "passive"))
      (node (ref "C46") (pin "2") (pinfunction "2_2") (pintype "passive"))
      (node (ref "C47") (pin "1") (pinfunction "1_1") (pintype "passive"))
      (node (ref "C48") (pin "1") (pinfunction "1_1") (pintype "passive"))
      (node (ref "C5") (pin "2") (pinfunction "2_2") (pintype "passive"))
      (node (ref "C6") (pin "2") (pinfunction "2_2") (pintype "passive"))
      (node (ref "C7") (pin "1") (pinfunction "1_1") (pintype "passive"))
      (node (ref "C8") (pin "1") (pinfunction "1_1") (pintype "passive"))
      (node (ref "C9") (pin "1") (pinfunction "1_1") (pintype "passive"))
      (node (ref "JP1") (pin "1") (pinfunction "1_1") (pintype "passive"))
      (node (ref "LED1") (pin "2") (pinfunction "K_2") (pintype "passive"))
      (node (ref "LED2") (pin "2") (pinfunction "K_2") (pintype "passive"))
      (node (ref "Q1") (pin "2") (pinfunction "E_2") (pintype "passive"))
      (node (ref "R10") (pin "2") (pinfunction "2_2") (pintype "passive"))
      (node (ref "R13") (pin "2") (pinfunction "2_2") (pintype "passive"))
      (node (ref "R4") (pin "1") (pinfunction "1_1") (pintype "passive"))
      (node (ref "R6") (pin "1") (pinfunction "1_1") (pintype "passive"))
      (node (ref "SW2") (pin "2") (pinfunction "2_2") (pintype "passive"))
      (node (ref "U1") (pin "A1") (pinfunction "VSS_1_A1") (pintype "power_in"))
      (node (ref "U1") (pin "A17") (pinfunction "VSS_1_A17") (pintype "power_in"))
      (node (ref "U1") (pin "B2") (pinfunction "VSS_1_B2") (pintype "power_in"))
      (node (ref "U1") (pin "B6") (pinfunction "VSS_1_B6") (pintype "power_in"))
      (node (ref "U1") (pin "C10") (pinfunction "VSS_1_C10") (pintype "power_in"))
      (node (ref "U1") (pin "C13") (pinfunction "VSS_1_C13") (pintype "power_in"))
      (node (ref "U1") (pin "C16") (pinfunction "VSS_1_C16") (pintype "power_in"))
      (node (ref "U1") (pin "F2") (pinfunction "VSS_1_F2") (pintype "power_in"))
      (node (ref "U1") (pin "G10") (pinfunction "VSS_2_G10") (pintype "power_in"))
      (node (ref "U1") (pin "G11") (pinfunction "VSS_2_G11") (pintype "power_in"))
      (node (ref "U1") (pin "G16") (pinfunction "VSS_2_G16") (pintype "power_in"))
      (node (ref "U1") (pin "G7") (pinfunction "VSS_2_G7") (pintype "power_in"))
      (node (ref "U1") (pin "G8") (pinfunction "VSS_2_G8") (pintype "power_in"))
      (node (ref "U1") (pin "G9") (pinfunction "VSS_2_G9") (pintype "power_in"))
      (node (ref "U1") (pin "H10") (pinfunction "VSS_2_H10") (pintype "power_in"))
      (node (ref "U1") (pin "H11") (pinfunction "VSS_3_H11") (pintype "power_in"))
      (node (ref "U1") (pin "H7") (pinfunction "VSS_2_H7") (pintype "power_in"))
      (node (ref "U1") (pin "H8") (pinfunction "VSS_2_H8") (pintype "power_in"))
      (node (ref "U1") (pin "H9") (pinfunction "VSS_2_H9") (pintype "power_in"))
      (node (ref "U1") (pin "J10") (pinfunction "VSS_3_J10") (pintype "power_in"))
      (node (ref "U1") (pin "J11") (pinfunction "VSS_3_J11") (pintype "power_in"))
      (node (ref "U1") (pin "J16") (pinfunction "VSS_1_J16") (pintype "power_in"))
      (node (ref "U1") (pin "J17") (pinfunction "VSS_1_J17") (pintype "power_in"))
      (node (ref "U1") (pin "J3") (pinfunction "VSS_1_J3") (pintype "power_in"))
      (node (ref "U1") (pin "J7") (pinfunction "VSS_3_J7") (pintype "power_in"))
      (node (ref "U1") (pin "J8") (pinfunction "VSS_3_J8") (pintype "power_in"))
      (node (ref "U1") (pin "J9") (pinfunction "VSS_3_J9") (pintype "power_in"))
      (node (ref "U1") (pin "K10") (pinfunction "VSS_3_K10") (pintype "power_in"))
      (node (ref "U1") (pin "K11") (pinfunction "VSS_3_K11") (pintype "power_in"))
      (node (ref "U1") (pin "K15") (pinfunction "VSS_2_K15") (pintype "power_in"))
      (node (ref "U1") (pin "K7") (pinfunction "VSS_3_K7") (pintype "power_in"))
      (node (ref "U1") (pin "K8") (pinfunction "VSS_3_K8") (pintype "power_in"))
      (node (ref "U1") (pin "K9") (pinfunction "VSS_3_K9") (pintype "power_in"))
      (node (ref "U1") (pin "L10") (pinfunction "VSS_3_L10") (pintype "power_in"))
      (node (ref "U1") (pin "L11") (pinfunction "VSS_3_L11") (pintype "power_in"))
      (node (ref "U1") (pin "L15") (pinfunction "VSS_2_L15") (pintype "power_in"))
      (node (ref "U1") (pin "L7") (pinfunction "VSS_3_L7") (pintype "power_in"))
      (node (ref "U1") (pin "L8") (pinfunction "VSS_3_L8") (pintype "power_in"))
      (node (ref "U1") (pin "L9") (pinfunction "VSS_3_L9") (pintype "power_in"))
      (node (ref "U1") (pin "M15") (pinfunction "VSS_2_M15") (pintype "power_in"))
      (node (ref "U1") (pin "N1") (pinfunction "VREF-_N1") (pintype "input"))
      (node (ref "U1") (pin "N16") (pinfunction "VSS_1_N16") (pintype "power_in"))
      (node (ref "U1") (pin "P1") (pinfunction "VSSA_P1") (pintype "power_in"))
      (node (ref "U1") (pin "R4") (pinfunction "VSS_1_R4") (pintype "power_in"))
      (node (ref "U1") (pin "R8") (pinfunction "VSS_2_R8") (pintype "power_in"))
      (node (ref "U1") (pin "T12") (pinfunction "VSS_1_T12") (pintype "power_in"))
      (node (ref "U1") (pin "U1") (pinfunction "VSS_2_U1") (pintype "power_in"))
      (node (ref "U1") (pin "U17") (pinfunction "VSS_1_U17") (pintype "power_in"))
      (node (ref "U2") (pin "A3") (pinfunction "VSS_A3") (pintype "power_in"))
      (node (ref "U2") (pin "B3") (pinfunction "VSSQ_B3") (pintype "power_in"))
      (node (ref "U2") (pin "B8") (pinfunction "VSSQ_B8") (pintype "power_in"))
      (node (ref "U2") (pin "C1") (pinfunction "VSSQ_C1") (pintype "power_in"))
      (node (ref "U2") (pin "D1") (pinfunction "VSSQ_D1") (pintype "power_in"))
      (node (ref "U2") (pin "E9") (pinfunction "VSSQ_E9") (pintype "power_in"))
      (node (ref "U2") (pin "F1") (pinfunction "VSS_F1") (pintype "power_in"))
      (node (ref "U2") (pin "L3") (pinfunction "VSS_L3") (pintype "power_in"))
      (node (ref "U2") (pin "L9") (pinfunction "VSSQ_L9") (pintype "power_in"))
      (node (ref "U2") (pin "M1") (pinfunction "VSSQ_M1") (pintype "power_in"))
      (node (ref "U2") (pin "N1") (pinfunction "VSSQ_N1") (pintype "power_in"))
      (node (ref "U2") (pin "P3") (pinfunction "VSSQ_P3") (pintype "power_in"))
      (node (ref "U2") (pin "P8") (pinfunction "VSSQ_P8") (pintype "power_in"))
      (node (ref "U2") (pin "R3") (pinfunction "VSS_R3") (pintype "power_in"))
      (node (ref "U3") (pin "4") (pinfunction "GND_4") (pintype "passive"))
      (node (ref "U3") (pin "9") (pinfunction "EP_9") (pintype "passive"))
      (node (ref "U4") (pin "59") (pinfunction "59_59") (pintype "passive"))
      (node (ref "U4") (pin "60") (pinfunction "60_60") (pintype "passive"))
      (node (ref "U4") (pin "61") (pinfunction "61_61") (pintype "passive"))
      (node (ref "U4") (pin "62") (pinfunction "62_62") (pintype "passive"))
      (node (ref "U5") (pin "1") (pinfunction "1_1") (pintype "passive"))
      (node (ref "U5") (pin "2") (pinfunction "2_2") (pintype "passive"))
      (node (ref "U5") (pin "61") (pinfunction "61_61") (pintype "passive"))
      (node (ref "U5") (pin "62") (pinfunction "62_62") (pintype "passive"))
      (node (ref "U6") (pin "21") (pinfunction "GND_21") (pintype "passive"))
      (node (ref "X1") (pin "2") (pinfunction "2_2") (pintype "passive"))
      (node (ref "X1") (pin "4") (pinfunction "4_4") (pintype "passive"))
    )
    (net (code "183") (name "Net-(C1-Pad2)") (class "Default")
      (node (ref "C1") (pin "2") (pinfunction "2_2") (pintype "passive"))
      (node (ref "U1") (pin "A7") (pinfunction "VCAP_A7") (pintype "power_in"))
    )
    (net (code "184") (name "Net-(C2-Pad2)") (class "Default")
      (node (ref "C2") (pin "2") (pinfunction "2_2") (pintype "passive"))
      (node (ref "U1") (pin "D17") (pinfunction "VCAP_D17") (pintype "power_in"))
    )
    (net (code "185") (name "Net-(C3-Pad2)") (class "Default")
      (node (ref "C3") (pin "2") (pinfunction "2_2") (pintype "passive"))
      (node (ref "U1") (pin "U11") (pinfunction "VCAP_U11") (pintype "power_in"))
    )
    (net (code "186") (name "Net-(D1-A)") (class "Default")
      (node (ref "D1") (pin "1") (pinfunction "A_1") (pintype "passive"))
      (node (ref "R3") (pin "1") (pinfunction "1_1") (pintype "passive"))
      (node (ref "SW1") (pin "2") (pinfunction "2_2") (pintype "passive"))
    )
    (net (code "187") (name "Net-(D1-K)") (class "Default")
      (node (ref "C34") (pin "1") (pinfunction "1_1") (pintype "passive"))
      (node (ref "D1") (pin "2") (pinfunction "K_2") (pintype "passive"))
      (node (ref "Q2") (pin "1") (pinfunction "B_1") (pintype "passive"))
    )
    (net (code "188") (name "Net-(LED2-A)") (class "Default")
      (node (ref "LED2") (pin "1") (pinfunction "A_1") (pintype "passive"))
      (node (ref "R7") (pin "2") (pinfunction "2_2") (pintype "passive"))
    )
    (net (code "189") (name "Net-(LED3-A)") (class "Default")
      (node (ref "LED3") (pin "1") (pinfunction "A_1") (pintype "passive"))
      (node (ref "R9") (pin "2") (pinfunction "2_2") (pintype "passive"))
    )
    (net (code "190") (name "Net-(Q1-B)") (class "Default")
      (node (ref "C29") (pin "1") (pinfunction "1_1") (pintype "passive"))
      (node (ref "Q1") (pin "1") (pinfunction "B_1") (pintype "passive"))
      (node (ref "R3") (pin "2") (pinfunction "2_2") (pintype "passive"))
      (node (ref "R4") (pin "2") (pinfunction "2_2") (pintype "passive"))
    )
    (net (code "191") (name "Net-(Q2-C)") (class "Default")
      (node (ref "Q2") (pin "3") (pinfunction "C_3") (pintype "passive"))
      (node (ref "R5") (pin "1") (pinfunction "1_1") (pintype "passive"))
    )
    (net (code "192") (name "Net-(U1A-PDR_ON)") (class "Default")
      (node (ref "R1") (pin "2") (pinfunction "2_2") (pintype "passive"))
      (node (ref "U1") (pin "E7") (pinfunction "PDR_ON_E7") (pintype "input"))
    )
    (net (code "193") (name "Net-(U6-FB2)") (class "Default")
      (node (ref "C42") (pin "1") (pinfunction "1_1") (pintype "passive"))
      (node (ref "R10") (pin "1") (pinfunction "1_1") (pintype "passive"))
      (node (ref "R12") (pin "2") (pinfunction "2_2") (pintype "passive"))
      (node (ref "U6") (pin "3") (pinfunction "FB2_3") (pintype "passive"))
    )
    (net (code "194") (name "Net-(U6-FB3)") (class "Default")
      (node (ref "C41") (pin "1") (pinfunction "1_1") (pintype "passive"))
      (node (ref "R11") (pin "2") (pinfunction "2_2") (pintype "passive"))
      (node (ref "R13") (pin "1") (pinfunction "1_1") (pintype "passive"))
      (node (ref "U6") (pin "2") (pinfunction "FB3_2") (pintype "passive"))
    )
    (net (code "195") (name "Net-(U6-SW2)") (class "Default")
      (node (ref "L2") (pin "2") (pinfunction "2_2") (pintype "passive"))
      (node (ref "U6") (pin "6") (pinfunction "SW2_6") (pintype "passive"))
    )
    (net (code "196") (name "Net-(U6-SW3)") (class "Default")
      (node (ref "L1") (pin "2") (pinfunction "2_2") (pintype "passive"))
      (node (ref "U6") (pin "20") (pinfunction "SW3_20") (pintype "passive"))
    )
    (net (code "197") (name "unconnected-(U1F-NC-PadE1)") (class "Default")
      (node (ref "U1") (pin "E1") (pinfunction "NC_E1") (pintype "passive+no_connect"))
    )
    (net (code "198") (name "unconnected-(U1F-NC-PadK16)") (class "Default")
      (node (ref "U1") (pin "K16") (pinfunction "NC_K16") (pintype "passive+no_connect"))
    )
    (net (code "199") (name "unconnected-(U1F-NC-PadK17)") (class "Default")
      (node (ref "U1") (pin "K17") (pinfunction "NC_K17") (pintype "passive+no_connect"))
    )
    (net (code "200") (name "unconnected-(U1F-NC-PadL16)") (class "Default")
      (node (ref "U1") (pin "L16") (pinfunction "NC_L16") (pintype "passive+no_connect"))
    )
    (net (code "201") (name "unconnected-(U1F-NC-PadL17)") (class "Default")
      (node (ref "U1") (pin "L17") (pinfunction "NC_L17") (pintype "passive+no_connect"))
    )
    (net (code "202") (name "unconnected-(U1F-NC-PadM16)") (class "Default")
      (node (ref "U1") (pin "M16") (pinfunction "NC_M16") (pintype "passive+no_connect"))
    )
    (net (code "203") (name "unconnected-(U1F-NC-PadM17)") (class "Default")
      (node (ref "U1") (pin "M17") (pinfunction "NC_M17") (pintype "passive+no_connect"))
    )
    (net (code "204") (name "unconnected-(U1F-NC-PadN17)") (class "Default")
      (node (ref "U1") (pin "N17") (pinfunction "NC_N17") (pintype "passive+no_connect"))
    )
    (net (code "205") (name "unconnected-(U1F-NC1-PadF1)") (class "Default")
      (node (ref "U1") (pin "F1") (pinfunction "NC1_F1") (pintype "passive+no_connect"))
    )
    (net (code "206") (name "unconnected-(U1F-NC2-PadG2)") (class "Default")
      (node (ref "U1") (pin "G2") (pinfunction "NC2_G2") (pintype "passive+no_connect"))
    )
    (net (code "207") (name "unconnected-(U2-NU-PadK2)") (class "Default")
      (node (ref "U2") (pin "K2") (pinfunction "NU_K2") (pintype "bidirectional+no_connect"))
    )
    (net (code "208") (name "unconnected-(U6-EN1-Pad9)") (class "Default")
      (node (ref "U6") (pin "9") (pinfunction "EN1_9") (pintype "passive+no_connect"))
    )
    (net (code "209") (name "unconnected-(U6-FB1-Pad14)") (class "Default")
      (node (ref "U6") (pin "14") (pinfunction "FB1_14") (pintype "passive+no_connect"))
    )
    (net (code "210") (name "unconnected-(U6-NC-Pad1)") (class "Default")
      (node (ref "U6") (pin "1") (pinfunction "NC_1") (pintype "passive+no_connect"))
    )
    (net (code "211") (name "unconnected-(U6-NC-Pad4)") (class "Default")
      (node (ref "U6") (pin "4") (pinfunction "NC_4") (pintype "passive+no_connect"))
    )
    (net (code "212") (name "unconnected-(U6-NC-Pad5)") (class "Default")
      (node (ref "U6") (pin "5") (pinfunction "NC_5") (pintype "passive+no_connect"))
    )
    (net (code "213") (name "unconnected-(U6-NC-Pad12)") (class "Default")
      (node (ref "U6") (pin "12") (pinfunction "NC_12") (pintype "passive+no_connect"))
    )
    (net (code "214") (name "unconnected-(U6-NC-Pad13)") (class "Default")
      (node (ref "U6") (pin "13") (pinfunction "NC_13") (pintype "passive+no_connect"))
    )
    (net (code "215") (name "unconnected-(U6-NC-Pad15)") (class "Default")
      (node (ref "U6") (pin "15") (pinfunction "NC_15") (pintype "passive+no_connect"))
    )
    (net (code "216") (name "unconnected-(U6-NC-Pad16)") (class "Default")
      (node (ref "U6") (pin "16") (pinfunction "NC_16") (pintype "passive+no_connect"))
    )
    (net (code "217") (name "unconnected-(U6-NC-Pad17)") (class "Default")
      (node (ref "U6") (pin "17") (pinfunction "NC_17") (pintype "passive+no_connect"))
    )
    (net (code "218") (name "unconnected-(U6-SW1-Pad11)") (class "Default")
      (node (ref "U6") (pin "11") (pinfunction "SW1_11") (pintype "passive+no_connect"))
    )
    (net (code "219") (name "unconnected-(U6-VIN1-Pad10)") (class "Default")
      (node (ref "U6") (pin "10") (pinfunction "VIN1_10") (pintype "passive+no_connect"))
    )
  )
)
